# MICROCODE.net
KiCad netlist of a schematic drawn in EAGLE
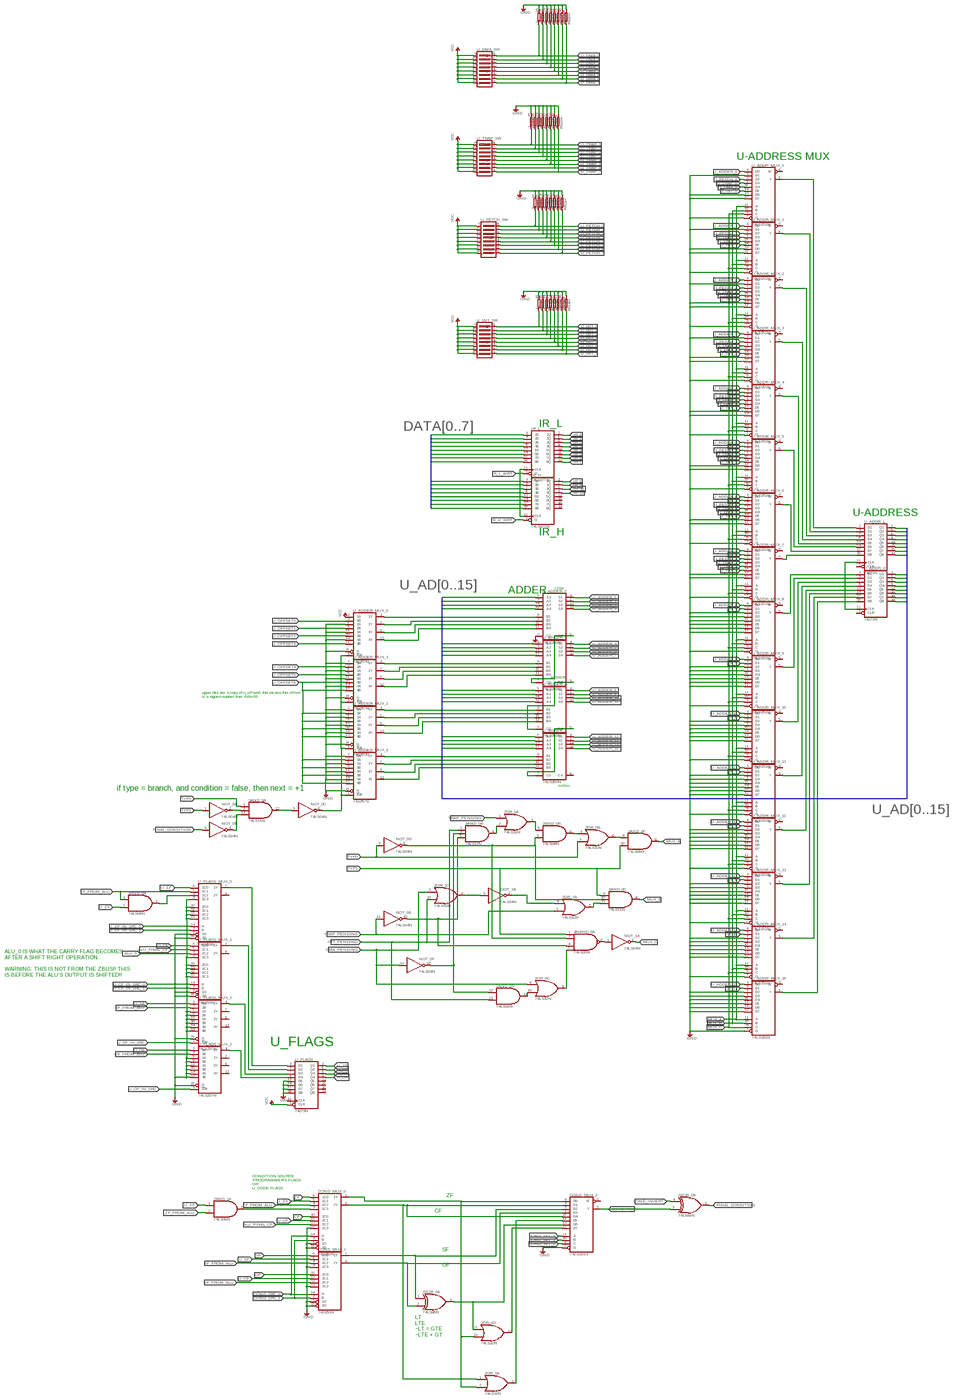
[diagram p0: schematic, sheet 1, overview]
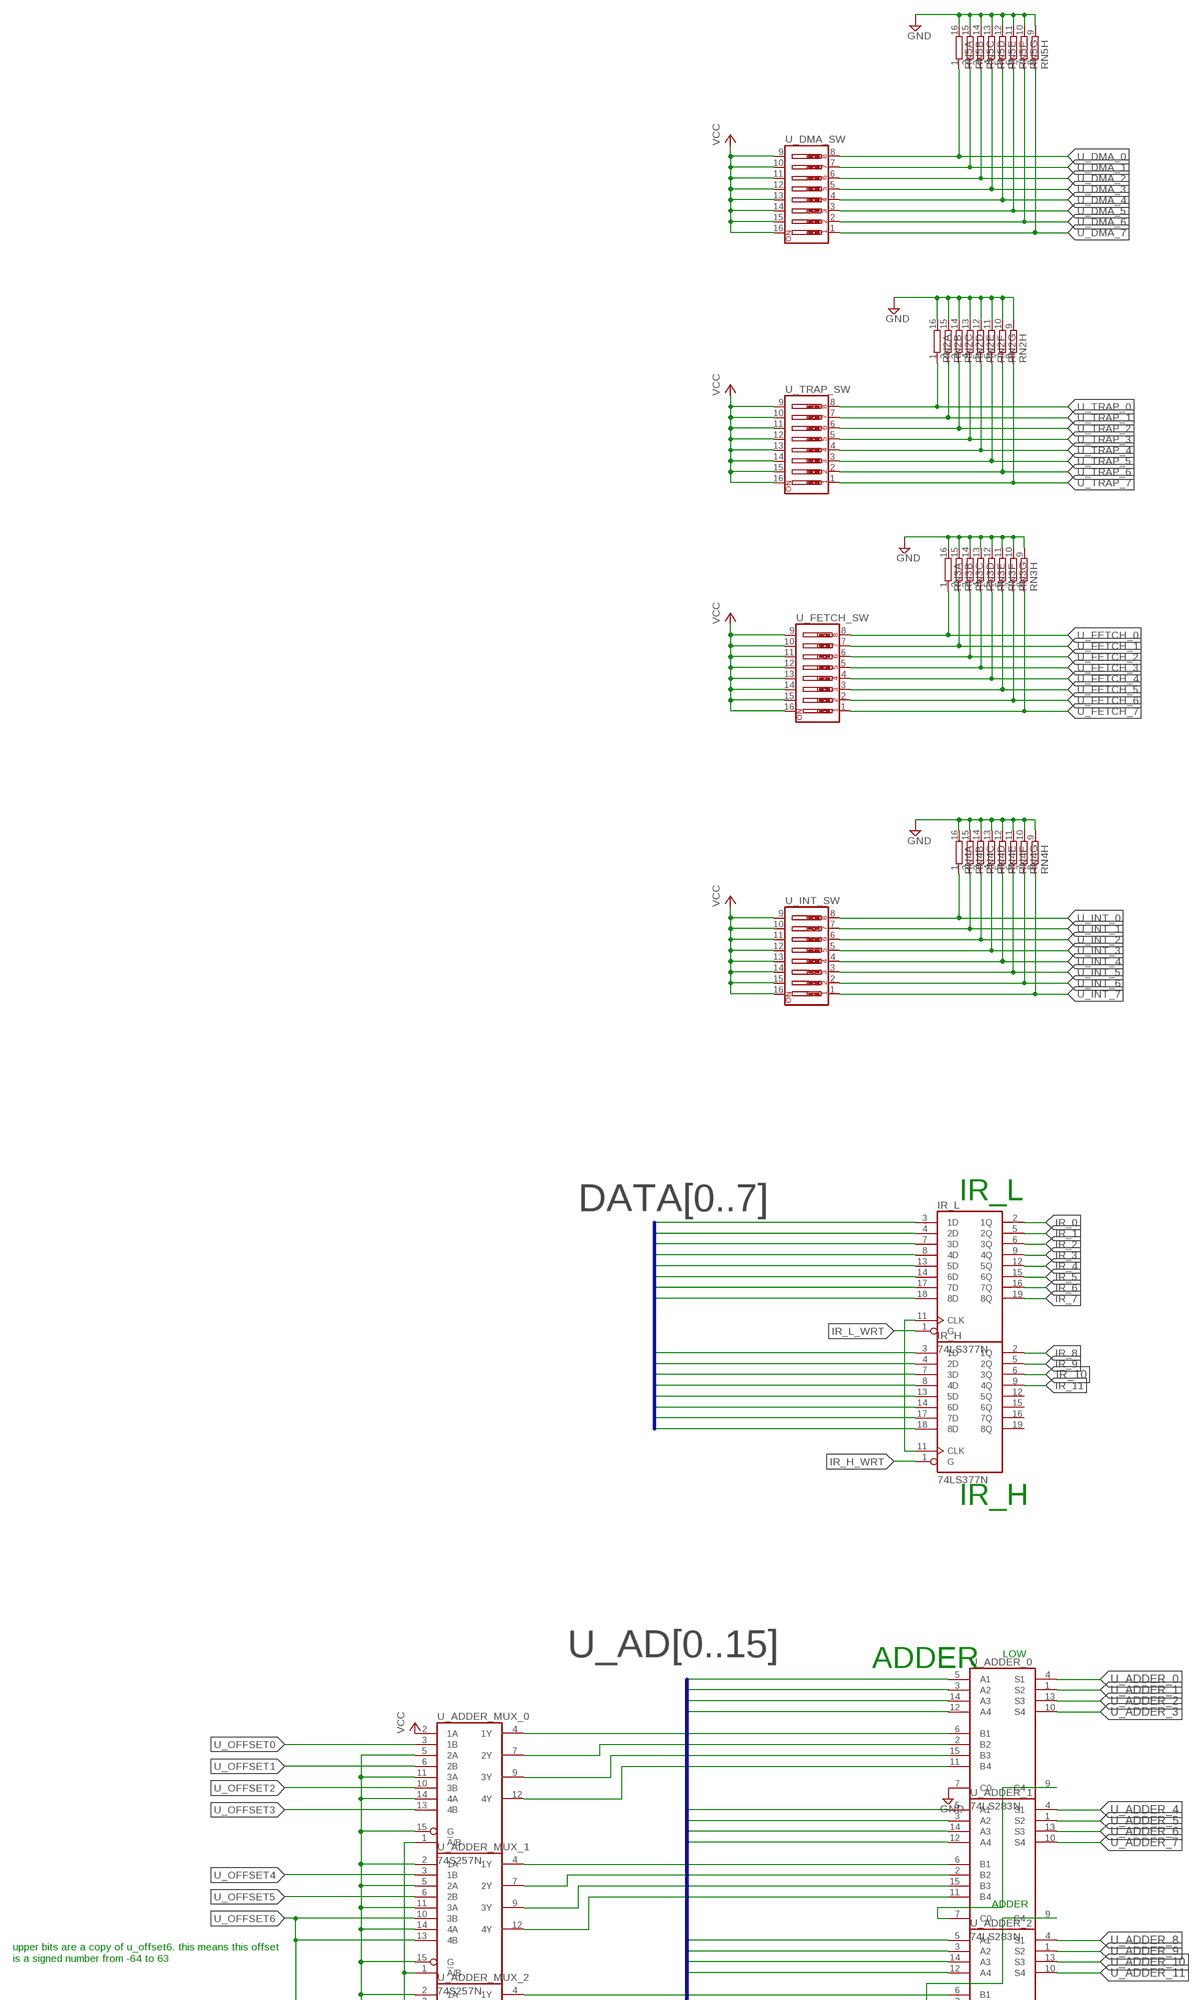
[diagram p1: schematic, sheet 1, part 1 of 4]
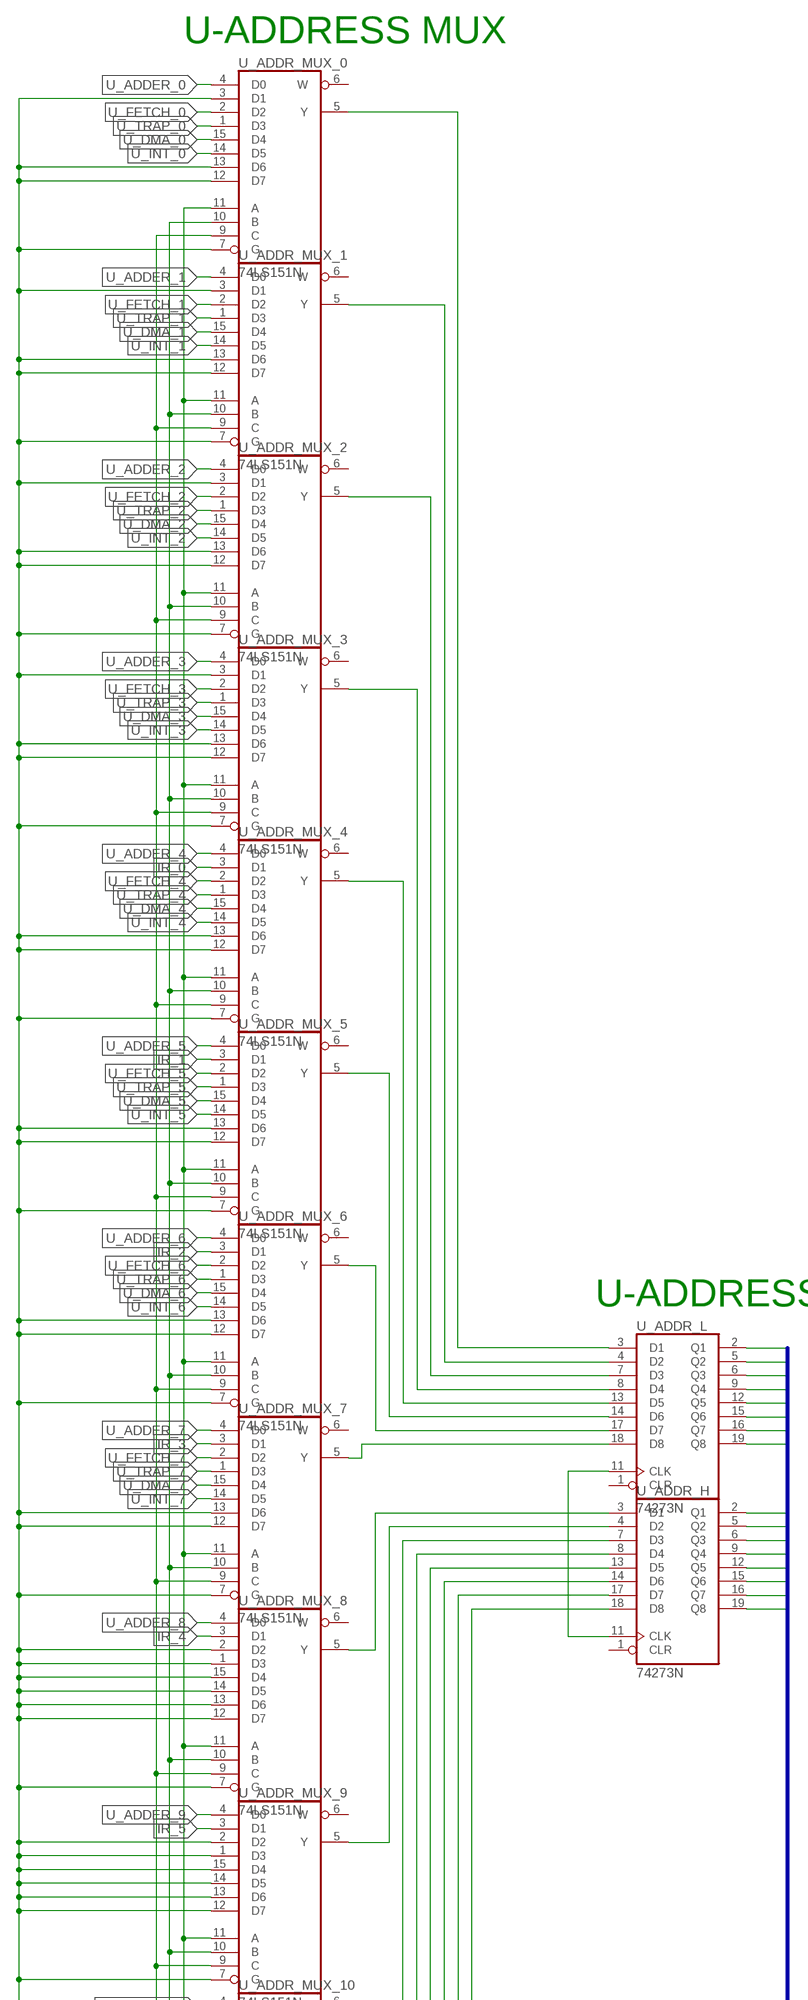
[diagram p2: schematic, sheet 1, part 2 of 4]
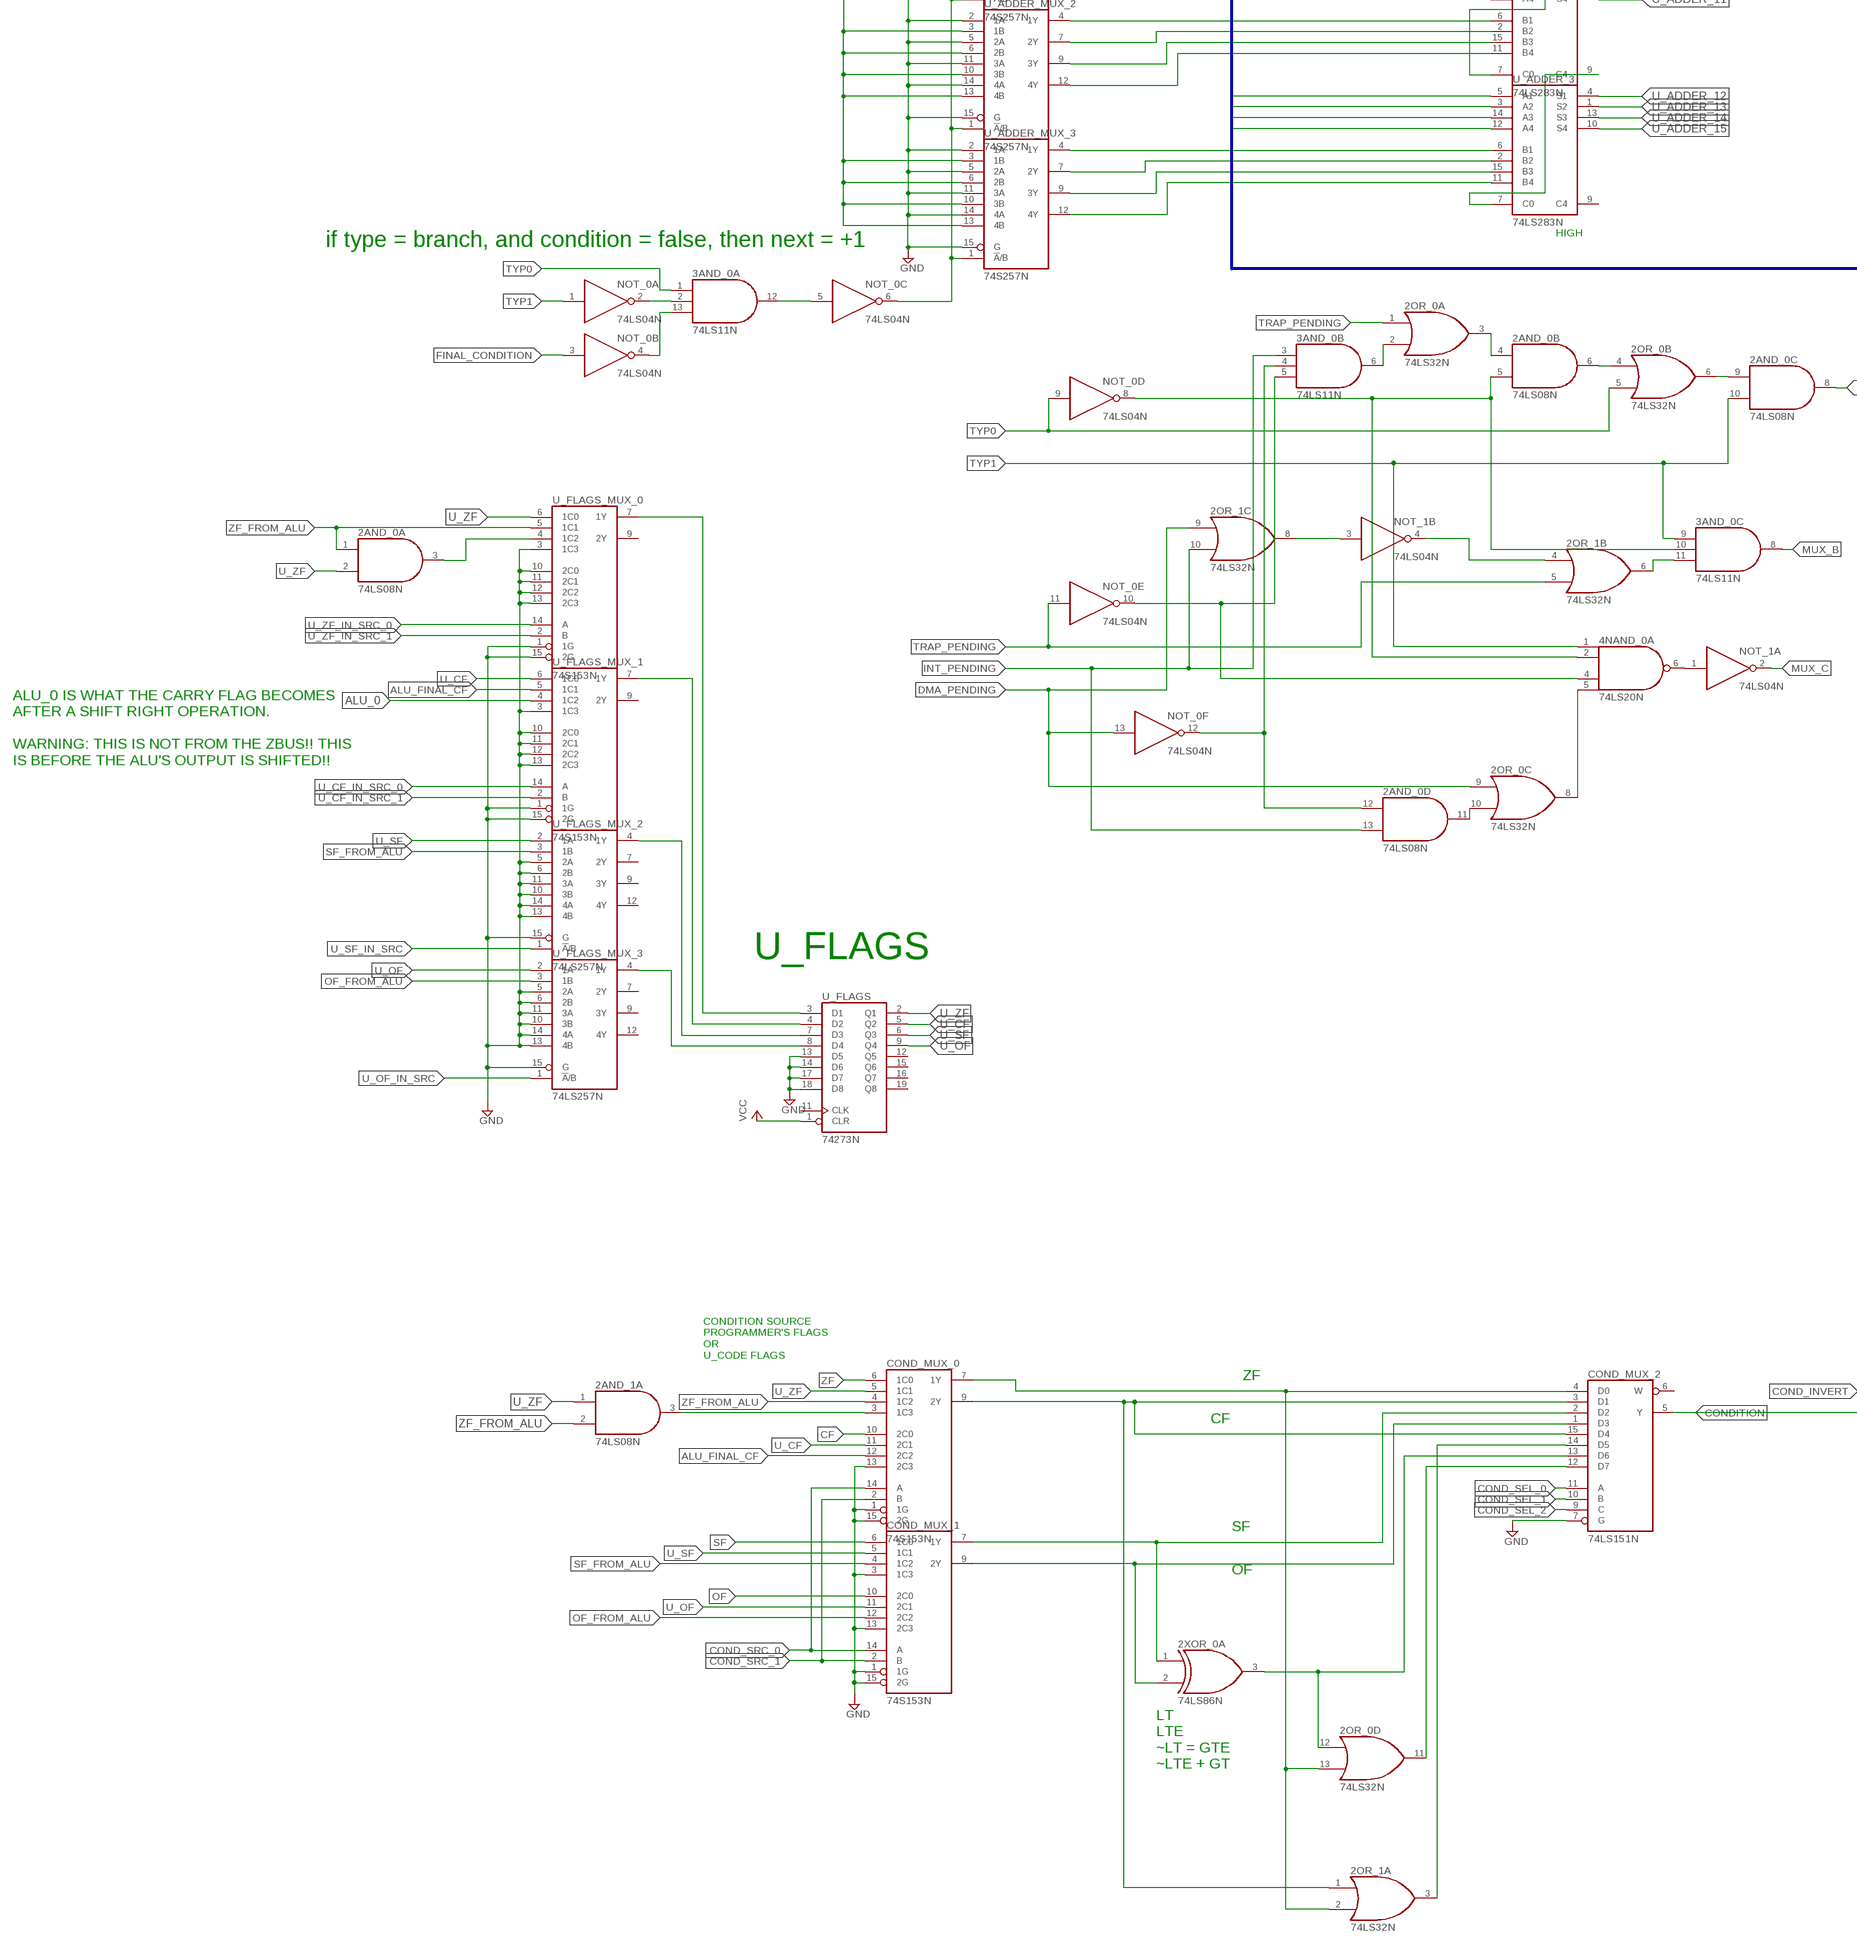
[diagram p3: schematic, sheet 1, part 3 of 4]
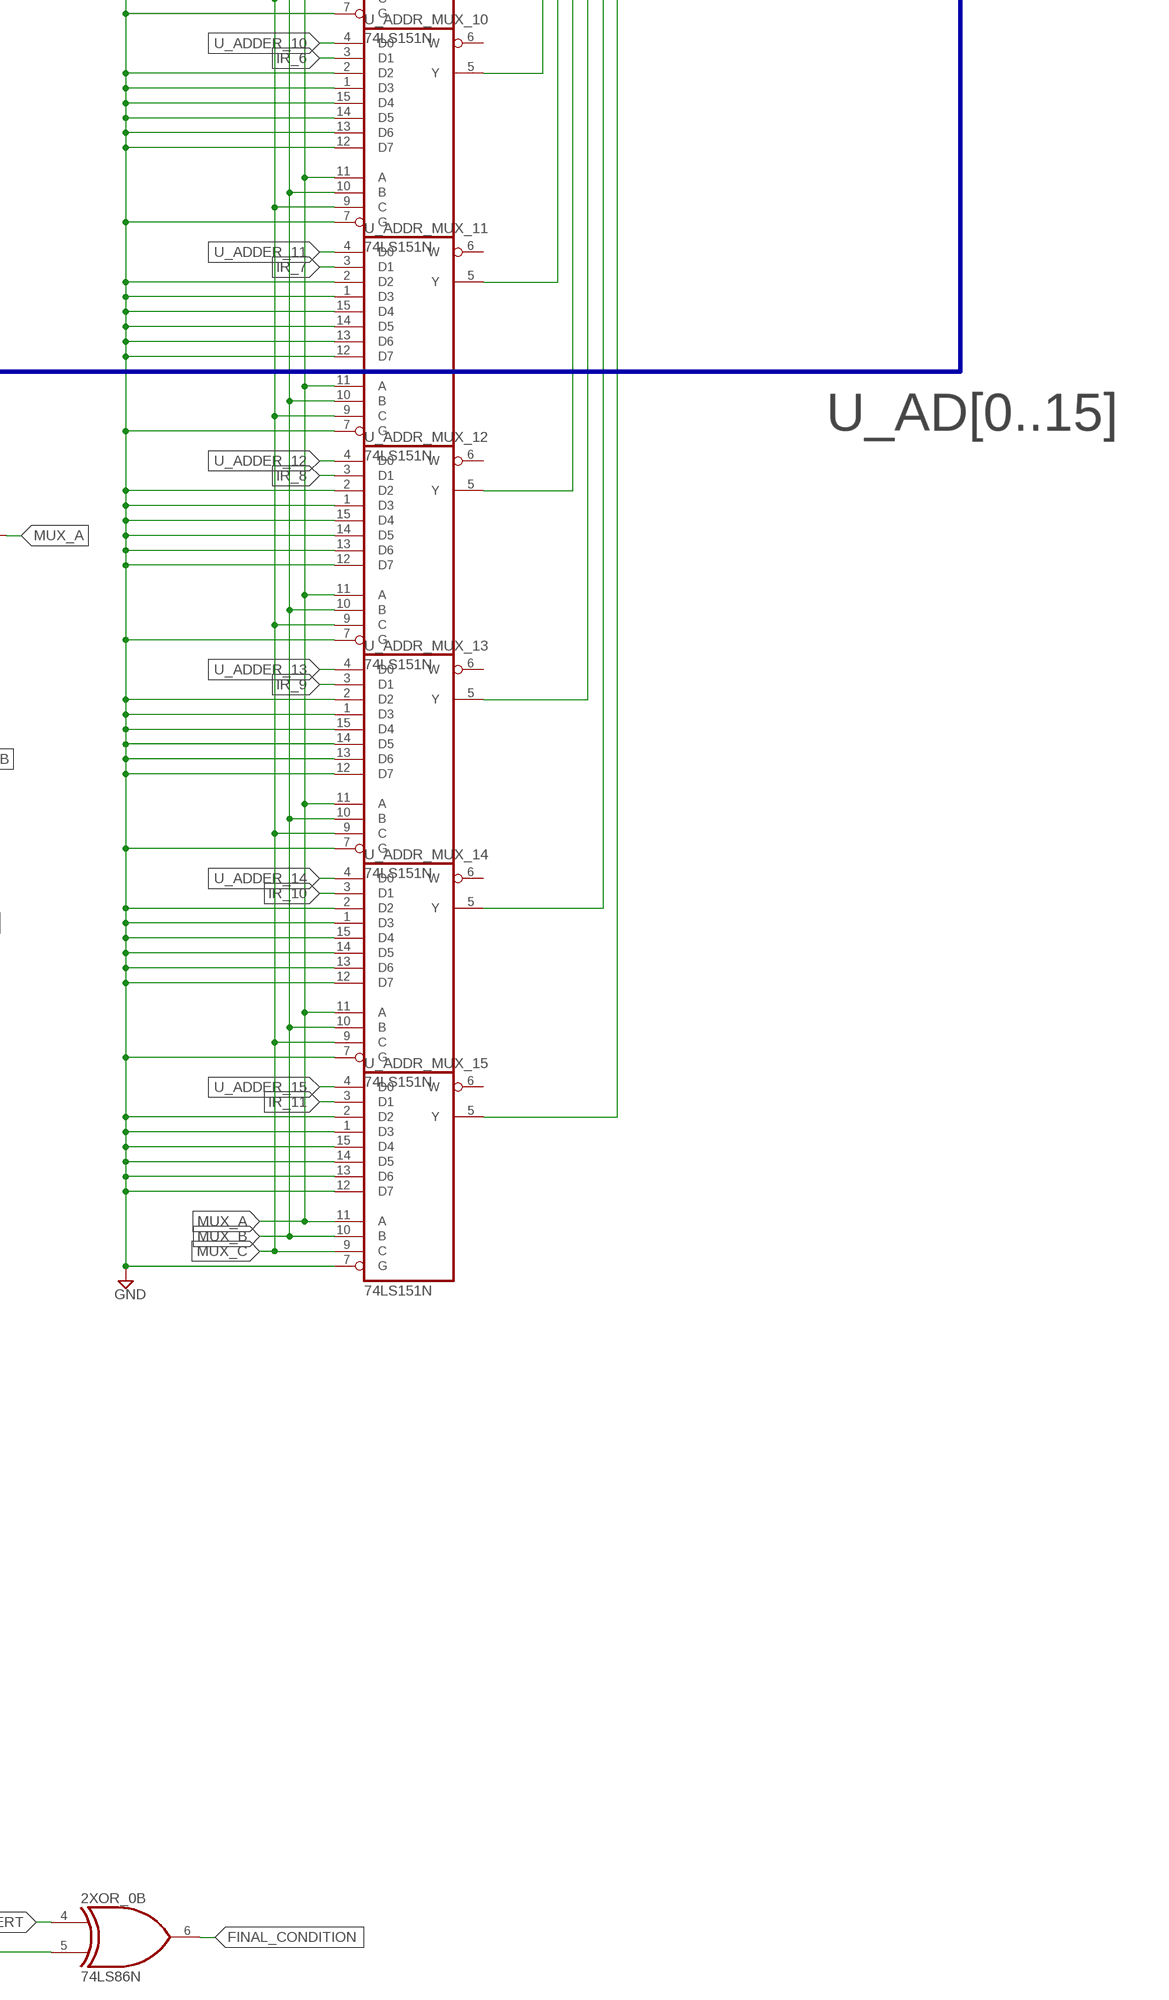
[diagram p4: schematic, sheet 1, part 4 of 4]

(export (version "E")
  (design (tool "Eeschema 10.0.6"))
  (components
    (comp (ref "2AND_0")
      (value "74LS08N")
      (footprint "eagle-import:DIL14")
      (libsource (lib "eagle-import") (part "7408NLS"))
    )
    (comp (ref "2AND_1")
      (value "74LS08N")
      (footprint "eagle-import:DIL14")
      (libsource (lib "eagle-import") (part "7408NLS"))
    )
    (comp (ref "2OR_0")
      (value "74LS32N")
      (footprint "eagle-import:DIL14")
      (libsource (lib "eagle-import") (part "7432NLS"))
    )
    (comp (ref "2OR_1")
      (value "74LS32N")
      (footprint "eagle-import:DIL14")
      (libsource (lib "eagle-import") (part "7432NLS"))
    )
    (comp (ref "2XOR_0")
      (value "74LS86N")
      (footprint "eagle-import:DIL14")
      (libsource (lib "eagle-import") (part "7486NLS"))
    )
    (comp (ref "3AND_0")
      (value "74LS11N")
      (footprint "eagle-import:DIL14")
      (libsource (lib "eagle-import") (part "7411NLS"))
    )
    (comp (ref "4NAND_0")
      (value "74LS20N")
      (footprint "eagle-import:DIL14")
      (libsource (lib "eagle-import") (part "7420NLS"))
    )
    (comp (ref "COND_MUX_0")
      (value "74S153N")
      (footprint "eagle-import:DIL16")
      (libsource (lib "eagle-import") (part "74153NS"))
    )
    (comp (ref "COND_MUX_1")
      (value "74S153N")
      (footprint "eagle-import:DIL16")
      (libsource (lib "eagle-import") (part "74153NS"))
    )
    (comp (ref "COND_MUX_2")
      (value "74LS151N")
      (footprint "eagle-import:DIL16")
      (libsource (lib "eagle-import") (part "74151NLS"))
    )
    (comp (ref "IR_H")
      (value "74LS377N")
      (footprint "eagle-import:DIL20")
      (libsource (lib "eagle-import") (part "74377NLS"))
    )
    (comp (ref "IR_L")
      (value "74LS377N")
      (footprint "eagle-import:DIL20")
      (libsource (lib "eagle-import") (part "74377NLS"))
    )
    (comp (ref "NOT_0")
      (value "74LS04N")
      (footprint "eagle-import:DIL14")
      (libsource (lib "eagle-import") (part "7404NLS"))
    )
    (comp (ref "NOT_1")
      (value "74LS04N")
      (footprint "eagle-import:DIL14")
      (libsource (lib "eagle-import") (part "7404NLS"))
    )
    (comp (ref "RN2")
      (value "8R-N")
      (footprint "eagle-import:DIL16")
      (libsource (lib "eagle-import") (part "8R-N"))
    )
    (comp (ref "RN3")
      (value "8R-N")
      (footprint "eagle-import:DIL16")
      (libsource (lib "eagle-import") (part "8R-N"))
    )
    (comp (ref "RN4")
      (value "8R-N")
      (footprint "eagle-import:DIL16")
      (libsource (lib "eagle-import") (part "8R-N"))
    )
    (comp (ref "RN5")
      (value "8R-N")
      (footprint "eagle-import:DIL16")
      (libsource (lib "eagle-import") (part "8R-N"))
    )
    (comp (ref "U_ADDER_0")
      (value "74LS283N")
      (footprint "eagle-import:DIL16")
      (libsource (lib "eagle-import") (part "74283NLS"))
    )
    (comp (ref "U_ADDER_1")
      (value "74LS283N")
      (footprint "eagle-import:DIL16")
      (libsource (lib "eagle-import") (part "74283NLS"))
    )
    (comp (ref "U_ADDER_2")
      (value "74LS283N")
      (footprint "eagle-import:DIL16")
      (libsource (lib "eagle-import") (part "74283NLS"))
    )
    (comp (ref "U_ADDER_3")
      (value "74LS283N")
      (footprint "eagle-import:DIL16")
      (libsource (lib "eagle-import") (part "74283NLS"))
    )
    (comp (ref "U_ADDER_MUX_0")
      (value "74S257N")
      (footprint "eagle-import:DIL16")
      (libsource (lib "eagle-import") (part "74257NS"))
    )
    (comp (ref "U_ADDER_MUX_1")
      (value "74S257N")
      (footprint "eagle-import:DIL16")
      (libsource (lib "eagle-import") (part "74257NS"))
    )
    (comp (ref "U_ADDER_MUX_2")
      (value "74S257N")
      (footprint "eagle-import:DIL16")
      (libsource (lib "eagle-import") (part "74257NS"))
    )
    (comp (ref "U_ADDER_MUX_3")
      (value "74S257N")
      (footprint "eagle-import:DIL16")
      (libsource (lib "eagle-import") (part "74257NS"))
    )
    (comp (ref "U_ADDR_H")
      (value "74273N")
      (footprint "eagle-import:DIL20")
      (libsource (lib "eagle-import") (part "74273N"))
    )
    (comp (ref "U_ADDR_L")
      (value "74273N")
      (footprint "eagle-import:DIL20")
      (libsource (lib "eagle-import") (part "74273N"))
    )
    (comp (ref "U_ADDR_MUX_0")
      (value "74LS151N")
      (footprint "eagle-import:DIL16")
      (libsource (lib "eagle-import") (part "74151NLS"))
    )
    (comp (ref "U_ADDR_MUX_1")
      (value "74LS151N")
      (footprint "eagle-import:DIL16")
      (libsource (lib "eagle-import") (part "74151NLS"))
    )
    (comp (ref "U_ADDR_MUX_2")
      (value "74LS151N")
      (footprint "eagle-import:DIL16")
      (libsource (lib "eagle-import") (part "74151NLS"))
    )
    (comp (ref "U_ADDR_MUX_3")
      (value "74LS151N")
      (footprint "eagle-import:DIL16")
      (libsource (lib "eagle-import") (part "74151NLS"))
    )
    (comp (ref "U_ADDR_MUX_4")
      (value "74LS151N")
      (footprint "eagle-import:DIL16")
      (libsource (lib "eagle-import") (part "74151NLS"))
    )
    (comp (ref "U_ADDR_MUX_5")
      (value "74LS151N")
      (footprint "eagle-import:DIL16")
      (libsource (lib "eagle-import") (part "74151NLS"))
    )
    (comp (ref "U_ADDR_MUX_6")
      (value "74LS151N")
      (footprint "eagle-import:DIL16")
      (libsource (lib "eagle-import") (part "74151NLS"))
    )
    (comp (ref "U_ADDR_MUX_7")
      (value "74LS151N")
      (footprint "eagle-import:DIL16")
      (libsource (lib "eagle-import") (part "74151NLS"))
    )
    (comp (ref "U_ADDR_MUX_8")
      (value "74LS151N")
      (footprint "eagle-import:DIL16")
      (libsource (lib "eagle-import") (part "74151NLS"))
    )
    (comp (ref "U_ADDR_MUX_9")
      (value "74LS151N")
      (footprint "eagle-import:DIL16")
      (libsource (lib "eagle-import") (part "74151NLS"))
    )
    (comp (ref "U_ADDR_MUX_10")
      (value "74LS151N")
      (footprint "eagle-import:DIL16")
      (libsource (lib "eagle-import") (part "74151NLS"))
    )
    (comp (ref "U_ADDR_MUX_11")
      (value "74LS151N")
      (footprint "eagle-import:DIL16")
      (libsource (lib "eagle-import") (part "74151NLS"))
    )
    (comp (ref "U_ADDR_MUX_12")
      (value "74LS151N")
      (footprint "eagle-import:DIL16")
      (libsource (lib "eagle-import") (part "74151NLS"))
    )
    (comp (ref "U_ADDR_MUX_13")
      (value "74LS151N")
      (footprint "eagle-import:DIL16")
      (libsource (lib "eagle-import") (part "74151NLS"))
    )
    (comp (ref "U_ADDR_MUX_14")
      (value "74LS151N")
      (footprint "eagle-import:DIL16")
      (libsource (lib "eagle-import") (part "74151NLS"))
    )
    (comp (ref "U_ADDR_MUX_15")
      (value "74LS151N")
      (footprint "eagle-import:DIL16")
      (libsource (lib "eagle-import") (part "74151NLS"))
    )
    (comp (ref "U_DMA_SW")
      (value "SW_DIP-8")
      (footprint "eagle-import:EDG-08")
      (libsource (lib "eagle-import") (part "SW_DIP-8"))
    )
    (comp (ref "U_FETCH_SW")
      (value "SW_DIP-8")
      (footprint "eagle-import:EDG-08")
      (libsource (lib "eagle-import") (part "SW_DIP-8"))
    )
    (comp (ref "U_FLAGS")
      (value "74273N")
      (footprint "eagle-import:DIL20")
      (libsource (lib "eagle-import") (part "74273N"))
    )
    (comp (ref "U_FLAGS_MUX_0")
      (value "74S153N")
      (footprint "eagle-import:DIL16")
      (libsource (lib "eagle-import") (part "74153NS"))
    )
    (comp (ref "U_FLAGS_MUX_1")
      (value "74S153N")
      (footprint "eagle-import:DIL16")
      (libsource (lib "eagle-import") (part "74153NS"))
    )
    (comp (ref "U_FLAGS_MUX_2")
      (value "74LS257N")
      (footprint "eagle-import:DIL16")
      (libsource (lib "eagle-import") (part "74257NLS"))
    )
    (comp (ref "U_FLAGS_MUX_3")
      (value "74LS257N")
      (footprint "eagle-import:DIL16")
      (libsource (lib "eagle-import") (part "74257NLS"))
    )
    (comp (ref "U_INT_SW")
      (value "SW_DIP-8")
      (footprint "eagle-import:EDG-08")
      (libsource (lib "eagle-import") (part "SW_DIP-8"))
    )
    (comp (ref "U_TRAP_SW")
      (value "SW_DIP-8")
      (footprint "eagle-import:EDG-08")
      (libsource (lib "eagle-import") (part "SW_DIP-8"))
    )
  )
  (nets
    (net (code "1") (name "/DATA0") (class "Default")
      (node (ref "IR_H") (pin "3") (pinfunction "1D_3") (pintype "input"))
      (node (ref "IR_L") (pin "3") (pinfunction "1D_3") (pintype "input"))
    )
    (net (code "2") (name "/DATA1") (class "Default")
      (node (ref "IR_H") (pin "4") (pinfunction "2D_4") (pintype "input"))
      (node (ref "IR_L") (pin "4") (pinfunction "2D_4") (pintype "input"))
    )
    (net (code "3") (name "/DATA2") (class "Default")
      (node (ref "IR_H") (pin "7") (pinfunction "3D_7") (pintype "input"))
      (node (ref "IR_L") (pin "7") (pinfunction "3D_7") (pintype "input"))
    )
    (net (code "4") (name "/DATA3") (class "Default")
      (node (ref "IR_H") (pin "8") (pinfunction "4D_8") (pintype "input"))
      (node (ref "IR_L") (pin "8") (pinfunction "4D_8") (pintype "input"))
    )
    (net (code "5") (name "/DATA4") (class "Default")
      (node (ref "IR_H") (pin "13") (pinfunction "5D_13") (pintype "input"))
      (node (ref "IR_L") (pin "13") (pinfunction "5D_13") (pintype "input"))
    )
    (net (code "6") (name "/DATA5") (class "Default")
      (node (ref "IR_H") (pin "14") (pinfunction "6D_14") (pintype "input"))
      (node (ref "IR_L") (pin "14") (pinfunction "6D_14") (pintype "input"))
    )
    (net (code "7") (name "/DATA6") (class "Default")
      (node (ref "IR_H") (pin "17") (pinfunction "7D_17") (pintype "input"))
      (node (ref "IR_L") (pin "17") (pinfunction "7D_17") (pintype "input"))
    )
    (net (code "8") (name "/DATA7") (class "Default")
      (node (ref "IR_H") (pin "18") (pinfunction "8D_18") (pintype "input"))
      (node (ref "IR_L") (pin "18") (pinfunction "8D_18") (pintype "input"))
    )
    (net (code "10") (name "/U_AD0") (class "Default")
      (node (ref "U_ADDER_0") (pin "5") (pinfunction "A1_5") (pintype "input"))
      (node (ref "U_ADDR_L") (pin "2") (pinfunction "Q1_2") (pintype "output"))
    )
    (net (code "11") (name "/U_AD1") (class "Default")
      (node (ref "U_ADDER_0") (pin "3") (pinfunction "A2_3") (pintype "input"))
      (node (ref "U_ADDR_L") (pin "5") (pinfunction "Q2_5") (pintype "output"))
    )
    (net (code "12") (name "/U_AD2") (class "Default")
      (node (ref "U_ADDER_0") (pin "14") (pinfunction "A3_14") (pintype "input"))
      (node (ref "U_ADDR_L") (pin "6") (pinfunction "Q3_6") (pintype "output"))
    )
    (net (code "13") (name "/U_AD3") (class "Default")
      (node (ref "U_ADDER_0") (pin "12") (pinfunction "A4_12") (pintype "input"))
      (node (ref "U_ADDR_L") (pin "9") (pinfunction "Q4_9") (pintype "output"))
    )
    (net (code "14") (name "/U_AD4") (class "Default")
      (node (ref "U_ADDER_1") (pin "5") (pinfunction "A1_5") (pintype "input"))
      (node (ref "U_ADDR_L") (pin "12") (pinfunction "Q5_12") (pintype "output"))
    )
    (net (code "15") (name "/U_AD5") (class "Default")
      (node (ref "U_ADDER_1") (pin "3") (pinfunction "A2_3") (pintype "input"))
      (node (ref "U_ADDR_L") (pin "15") (pinfunction "Q6_15") (pintype "output"))
    )
    (net (code "16") (name "/U_AD6") (class "Default")
      (node (ref "U_ADDER_1") (pin "14") (pinfunction "A3_14") (pintype "input"))
      (node (ref "U_ADDR_L") (pin "16") (pinfunction "Q7_16") (pintype "output"))
    )
    (net (code "17") (name "/U_AD7") (class "Default")
      (node (ref "U_ADDER_1") (pin "12") (pinfunction "A4_12") (pintype "input"))
      (node (ref "U_ADDR_L") (pin "19") (pinfunction "Q8_19") (pintype "output"))
    )
    (net (code "18") (name "/U_AD8") (class "Default")
      (node (ref "U_ADDER_2") (pin "5") (pinfunction "A1_5") (pintype "input"))
      (node (ref "U_ADDR_H") (pin "2") (pinfunction "Q1_2") (pintype "output"))
    )
    (net (code "19") (name "/U_AD9") (class "Default")
      (node (ref "U_ADDER_2") (pin "3") (pinfunction "A2_3") (pintype "input"))
      (node (ref "U_ADDR_H") (pin "5") (pinfunction "Q2_5") (pintype "output"))
    )
    (net (code "20") (name "/U_AD10") (class "Default")
      (node (ref "U_ADDER_2") (pin "14") (pinfunction "A3_14") (pintype "input"))
      (node (ref "U_ADDR_H") (pin "6") (pinfunction "Q3_6") (pintype "output"))
    )
    (net (code "21") (name "/U_AD11") (class "Default")
      (node (ref "U_ADDER_2") (pin "12") (pinfunction "A4_12") (pintype "input"))
      (node (ref "U_ADDR_H") (pin "9") (pinfunction "Q4_9") (pintype "output"))
    )
    (net (code "22") (name "/U_AD12") (class "Default")
      (node (ref "U_ADDER_3") (pin "5") (pinfunction "A1_5") (pintype "input"))
      (node (ref "U_ADDR_H") (pin "12") (pinfunction "Q5_12") (pintype "output"))
    )
    (net (code "23") (name "/U_AD13") (class "Default")
      (node (ref "U_ADDER_3") (pin "3") (pinfunction "A2_3") (pintype "input"))
      (node (ref "U_ADDR_H") (pin "15") (pinfunction "Q6_15") (pintype "output"))
    )
    (net (code "24") (name "/U_AD14") (class "Default")
      (node (ref "U_ADDER_3") (pin "14") (pinfunction "A3_14") (pintype "input"))
      (node (ref "U_ADDR_H") (pin "16") (pinfunction "Q7_16") (pintype "output"))
    )
    (net (code "25") (name "/U_AD15") (class "Default")
      (node (ref "U_ADDER_3") (pin "12") (pinfunction "A4_12") (pintype "input"))
      (node (ref "U_ADDR_H") (pin "19") (pinfunction "Q8_19") (pintype "output"))
    )
    (net (code "27") (name "ALU_0") (class "Default")
      (node (ref "U_FLAGS_MUX_1") (pin "4") (pinfunction "1C2_4") (pintype "input"))
    )
    (net (code "28") (name "ALU_FINAL_CF") (class "Default")
      (node (ref "COND_MUX_0") (pin "12") (pinfunction "2C2_12") (pintype "input"))
      (node (ref "U_FLAGS_MUX_1") (pin "5") (pinfunction "1C1_5") (pintype "input"))
    )
    (net (code "29") (name "CF") (class "Default")
      (node (ref "COND_MUX_0") (pin "10") (pinfunction "2C0_10") (pintype "input"))
    )
    (net (code "30") (name "CONDITION") (class "Default")
      (node (ref "2XOR_0") (pin "5") (pinfunction "I1_5") (pintype "input"))
      (node (ref "COND_MUX_2") (pin "5") (pinfunction "Y_5") (pintype "output"))
    )
    (net (code "31") (name "COND_INVERT") (class "Default")
      (node (ref "2XOR_0") (pin "4") (pinfunction "I0_4") (pintype "input"))
    )
    (net (code "32") (name "COND_SEL_0") (class "Default")
      (node (ref "COND_MUX_2") (pin "11") (pinfunction "A_11") (pintype "input"))
    )
    (net (code "33") (name "COND_SEL_1") (class "Default")
      (node (ref "COND_MUX_2") (pin "10") (pinfunction "B_10") (pintype "input"))
    )
    (net (code "34") (name "COND_SEL_2") (class "Default")
      (node (ref "COND_MUX_2") (pin "9") (pinfunction "C_9") (pintype "input"))
    )
    (net (code "35") (name "COND_SRC_0") (class "Default")
      (node (ref "COND_MUX_0") (pin "14") (pinfunction "A_14") (pintype "input"))
      (node (ref "COND_MUX_1") (pin "14") (pinfunction "A_14") (pintype "input"))
    )
    (net (code "36") (name "COND_SRC_1") (class "Default")
      (node (ref "COND_MUX_0") (pin "2") (pinfunction "B_2") (pintype "input"))
      (node (ref "COND_MUX_1") (pin "2") (pinfunction "B_2") (pintype "input"))
    )
    (net (code "37") (name "DMA_PENDING") (class "Default")
      (node (ref "2OR_0") (pin "9") (pinfunction "I0_9") (pintype "input"))
      (node (ref "2OR_1") (pin "9") (pinfunction "I0_9") (pintype "input"))
      (node (ref "NOT_0") (pin "13") (pinfunction "I_13") (pintype "input"))
    )
    (net (code "38") (name "FINAL_CONDITION") (class "Default")
      (node (ref "2XOR_0") (pin "6") (pinfunction "O_6") (pintype "output"))
      (node (ref "NOT_0") (pin "3") (pinfunction "I_3") (pintype "input"))
    )
    (net (code "39") (name "GND") (class "Default")
      (node (ref "COND_MUX_0") (pin "1") (pinfunction "1G_1") (pintype "input"))
      (node (ref "COND_MUX_0") (pin "13") (pinfunction "2C3_13") (pintype "input"))
      (node (ref "COND_MUX_0") (pin "15") (pinfunction "2G_15") (pintype "input"))
      (node (ref "COND_MUX_1") (pin "1") (pinfunction "1G_1") (pintype "input"))
      (node (ref "COND_MUX_1") (pin "13") (pinfunction "2C3_13") (pintype "input"))
      (node (ref "COND_MUX_1") (pin "15") (pinfunction "2G_15") (pintype "input"))
      (node (ref "COND_MUX_1") (pin "3") (pinfunction "1C3_3") (pintype "input"))
      (node (ref "COND_MUX_2") (pin "7") (pinfunction "G_7") (pintype "input"))
      (node (ref "RN2") (pin "10") (pinfunction "2_10") (pintype "passive"))
      (node (ref "RN2") (pin "11") (pinfunction "2_11") (pintype "passive"))
      (node (ref "RN2") (pin "12") (pinfunction "2_12") (pintype "passive"))
      (node (ref "RN2") (pin "13") (pinfunction "2_13") (pintype "passive"))
      (node (ref "RN2") (pin "14") (pinfunction "2_14") (pintype "passive"))
      (node (ref "RN2") (pin "15") (pinfunction "2_15") (pintype "passive"))
      (node (ref "RN2") (pin "16") (pinfunction "2_16") (pintype "passive"))
      (node (ref "RN2") (pin "9") (pinfunction "2_9") (pintype "passive"))
      (node (ref "RN3") (pin "10") (pinfunction "2_10") (pintype "passive"))
      (node (ref "RN3") (pin "11") (pinfunction "2_11") (pintype "passive"))
      (node (ref "RN3") (pin "12") (pinfunction "2_12") (pintype "passive"))
      (node (ref "RN3") (pin "13") (pinfunction "2_13") (pintype "passive"))
      (node (ref "RN3") (pin "14") (pinfunction "2_14") (pintype "passive"))
      (node (ref "RN3") (pin "15") (pinfunction "2_15") (pintype "passive"))
      (node (ref "RN3") (pin "16") (pinfunction "2_16") (pintype "passive"))
      (node (ref "RN3") (pin "9") (pinfunction "2_9") (pintype "passive"))
      (node (ref "RN4") (pin "10") (pinfunction "2_10") (pintype "passive"))
      (node (ref "RN4") (pin "11") (pinfunction "2_11") (pintype "passive"))
      (node (ref "RN4") (pin "12") (pinfunction "2_12") (pintype "passive"))
      (node (ref "RN4") (pin "13") (pinfunction "2_13") (pintype "passive"))
      (node (ref "RN4") (pin "14") (pinfunction "2_14") (pintype "passive"))
      (node (ref "RN4") (pin "15") (pinfunction "2_15") (pintype "passive"))
      (node (ref "RN4") (pin "16") (pinfunction "2_16") (pintype "passive"))
      (node (ref "RN4") (pin "9") (pinfunction "2_9") (pintype "passive"))
      (node (ref "RN5") (pin "10") (pinfunction "2_10") (pintype "passive"))
      (node (ref "RN5") (pin "11") (pinfunction "2_11") (pintype "passive"))
      (node (ref "RN5") (pin "12") (pinfunction "2_12") (pintype "passive"))
      (node (ref "RN5") (pin "13") (pinfunction "2_13") (pintype "passive"))
      (node (ref "RN5") (pin "14") (pinfunction "2_14") (pintype "passive"))
      (node (ref "RN5") (pin "15") (pinfunction "2_15") (pintype "passive"))
      (node (ref "RN5") (pin "16") (pinfunction "2_16") (pintype "passive"))
      (node (ref "RN5") (pin "9") (pinfunction "2_9") (pintype "passive"))
      (node (ref "U_ADDER_0") (pin "7") (pinfunction "C0_7") (pintype "input"))
      (node (ref "U_ADDER_MUX_0") (pin "11") (pinfunction "3A_11") (pintype "input"))
      (node (ref "U_ADDER_MUX_0") (pin "14") (pinfunction "4A_14") (pintype "input"))
      (node (ref "U_ADDER_MUX_0") (pin "15") (pinfunction "G_15") (pintype "input"))
      (node (ref "U_ADDER_MUX_0") (pin "5") (pinfunction "2A_5") (pintype "input"))
      (node (ref "U_ADDER_MUX_1") (pin "11") (pinfunction "3A_11") (pintype "input"))
      (node (ref "U_ADDER_MUX_1") (pin "14") (pinfunction "4A_14") (pintype "input"))
      (node (ref "U_ADDER_MUX_1") (pin "15") (pinfunction "G_15") (pintype "input"))
      (node (ref "U_ADDER_MUX_1") (pin "2") (pinfunction "1A_2") (pintype "input"))
      (node (ref "U_ADDER_MUX_1") (pin "5") (pinfunction "2A_5") (pintype "input"))
      (node (ref "U_ADDER_MUX_2") (pin "11") (pinfunction "3A_11") (pintype "input"))
      (node (ref "U_ADDER_MUX_2") (pin "14") (pinfunction "4A_14") (pintype "input"))
      (node (ref "U_ADDER_MUX_2") (pin "15") (pinfunction "G_15") (pintype "input"))
      (node (ref "U_ADDER_MUX_2") (pin "2") (pinfunction "1A_2") (pintype "input"))
      (node (ref "U_ADDER_MUX_2") (pin "5") (pinfunction "2A_5") (pintype "input"))
      (node (ref "U_ADDER_MUX_3") (pin "11") (pinfunction "3A_11") (pintype "input"))
      (node (ref "U_ADDER_MUX_3") (pin "14") (pinfunction "4A_14") (pintype "input"))
      (node (ref "U_ADDER_MUX_3") (pin "15") (pinfunction "G_15") (pintype "input"))
      (node (ref "U_ADDER_MUX_3") (pin "2") (pinfunction "1A_2") (pintype "input"))
      (node (ref "U_ADDER_MUX_3") (pin "5") (pinfunction "2A_5") (pintype "input"))
      (node (ref "U_ADDR_MUX_0") (pin "12") (pinfunction "D7_12") (pintype "input"))
      (node (ref "U_ADDR_MUX_0") (pin "13") (pinfunction "D6_13") (pintype "input"))
      (node (ref "U_ADDR_MUX_0") (pin "3") (pinfunction "D1_3") (pintype "input"))
      (node (ref "U_ADDR_MUX_0") (pin "7") (pinfunction "G_7") (pintype "input"))
      (node (ref "U_ADDR_MUX_1") (pin "12") (pinfunction "D7_12") (pintype "input"))
      (node (ref "U_ADDR_MUX_1") (pin "13") (pinfunction "D6_13") (pintype "input"))
      (node (ref "U_ADDR_MUX_1") (pin "3") (pinfunction "D1_3") (pintype "input"))
      (node (ref "U_ADDR_MUX_1") (pin "7") (pinfunction "G_7") (pintype "input"))
      (node (ref "U_ADDR_MUX_10") (pin "1") (pinfunction "D3_1") (pintype "input"))
      (node (ref "U_ADDR_MUX_10") (pin "12") (pinfunction "D7_12") (pintype "input"))
      (node (ref "U_ADDR_MUX_10") (pin "13") (pinfunction "D6_13") (pintype "input"))
      (node (ref "U_ADDR_MUX_10") (pin "14") (pinfunction "D5_14") (pintype "input"))
      (node (ref "U_ADDR_MUX_10") (pin "15") (pinfunction "D4_15") (pintype "input"))
      (node (ref "U_ADDR_MUX_10") (pin "2") (pinfunction "D2_2") (pintype "input"))
      (node (ref "U_ADDR_MUX_10") (pin "7") (pinfunction "G_7") (pintype "input"))
      (node (ref "U_ADDR_MUX_11") (pin "1") (pinfunction "D3_1") (pintype "input"))
      (node (ref "U_ADDR_MUX_11") (pin "12") (pinfunction "D7_12") (pintype "input"))
      (node (ref "U_ADDR_MUX_11") (pin "13") (pinfunction "D6_13") (pintype "input"))
      (node (ref "U_ADDR_MUX_11") (pin "14") (pinfunction "D5_14") (pintype "input"))
      (node (ref "U_ADDR_MUX_11") (pin "15") (pinfunction "D4_15") (pintype "input"))
      (node (ref "U_ADDR_MUX_11") (pin "2") (pinfunction "D2_2") (pintype "input"))
      (node (ref "U_ADDR_MUX_11") (pin "7") (pinfunction "G_7") (pintype "input"))
      (node (ref "U_ADDR_MUX_12") (pin "1") (pinfunction "D3_1") (pintype "input"))
      (node (ref "U_ADDR_MUX_12") (pin "12") (pinfunction "D7_12") (pintype "input"))
      (node (ref "U_ADDR_MUX_12") (pin "13") (pinfunction "D6_13") (pintype "input"))
      (node (ref "U_ADDR_MUX_12") (pin "14") (pinfunction "D5_14") (pintype "input"))
      (node (ref "U_ADDR_MUX_12") (pin "15") (pinfunction "D4_15") (pintype "input"))
      (node (ref "U_ADDR_MUX_12") (pin "2") (pinfunction "D2_2") (pintype "input"))
      (node (ref "U_ADDR_MUX_12") (pin "7") (pinfunction "G_7") (pintype "input"))
      (node (ref "U_ADDR_MUX_13") (pin "1") (pinfunction "D3_1") (pintype "input"))
      (node (ref "U_ADDR_MUX_13") (pin "12") (pinfunction "D7_12") (pintype "input"))
      (node (ref "U_ADDR_MUX_13") (pin "13") (pinfunction "D6_13") (pintype "input"))
      (node (ref "U_ADDR_MUX_13") (pin "14") (pinfunction "D5_14") (pintype "input"))
      (node (ref "U_ADDR_MUX_13") (pin "15") (pinfunction "D4_15") (pintype "input"))
      (node (ref "U_ADDR_MUX_13") (pin "2") (pinfunction "D2_2") (pintype "input"))
      (node (ref "U_ADDR_MUX_13") (pin "7") (pinfunction "G_7") (pintype "input"))
      (node (ref "U_ADDR_MUX_14") (pin "1") (pinfunction "D3_1") (pintype "input"))
      (node (ref "U_ADDR_MUX_14") (pin "12") (pinfunction "D7_12") (pintype "input"))
      (node (ref "U_ADDR_MUX_14") (pin "13") (pinfunction "D6_13") (pintype "input"))
      (node (ref "U_ADDR_MUX_14") (pin "14") (pinfunction "D5_14") (pintype "input"))
      (node (ref "U_ADDR_MUX_14") (pin "15") (pinfunction "D4_15") (pintype "input"))
      (node (ref "U_ADDR_MUX_14") (pin "2") (pinfunction "D2_2") (pintype "input"))
      (node (ref "U_ADDR_MUX_14") (pin "7") (pinfunction "G_7") (pintype "input"))
      (node (ref "U_ADDR_MUX_15") (pin "1") (pinfunction "D3_1") (pintype "input"))
      (node (ref "U_ADDR_MUX_15") (pin "12") (pinfunction "D7_12") (pintype "input"))
      (node (ref "U_ADDR_MUX_15") (pin "13") (pinfunction "D6_13") (pintype "input"))
      (node (ref "U_ADDR_MUX_15") (pin "14") (pinfunction "D5_14") (pintype "input"))
      (node (ref "U_ADDR_MUX_15") (pin "15") (pinfunction "D4_15") (pintype "input"))
      (node (ref "U_ADDR_MUX_15") (pin "2") (pinfunction "D2_2") (pintype "input"))
      (node (ref "U_ADDR_MUX_15") (pin "7") (pinfunction "G_7") (pintype "input"))
      (node (ref "U_ADDR_MUX_2") (pin "12") (pinfunction "D7_12") (pintype "input"))
      (node (ref "U_ADDR_MUX_2") (pin "13") (pinfunction "D6_13") (pintype "input"))
      (node (ref "U_ADDR_MUX_2") (pin "3") (pinfunction "D1_3") (pintype "input"))
      (node (ref "U_ADDR_MUX_2") (pin "7") (pinfunction "G_7") (pintype "input"))
      (node (ref "U_ADDR_MUX_3") (pin "12") (pinfunction "D7_12") (pintype "input"))
      (node (ref "U_ADDR_MUX_3") (pin "13") (pinfunction "D6_13") (pintype "input"))
      (node (ref "U_ADDR_MUX_3") (pin "3") (pinfunction "D1_3") (pintype "input"))
      (node (ref "U_ADDR_MUX_3") (pin "7") (pinfunction "G_7") (pintype "input"))
      (node (ref "U_ADDR_MUX_4") (pin "12") (pinfunction "D7_12") (pintype "input"))
      (node (ref "U_ADDR_MUX_4") (pin "13") (pinfunction "D6_13") (pintype "input"))
      (node (ref "U_ADDR_MUX_4") (pin "7") (pinfunction "G_7") (pintype "input"))
      (node (ref "U_ADDR_MUX_5") (pin "12") (pinfunction "D7_12") (pintype "input"))
      (node (ref "U_ADDR_MUX_5") (pin "13") (pinfunction "D6_13") (pintype "input"))
      (node (ref "U_ADDR_MUX_5") (pin "7") (pinfunction "G_7") (pintype "input"))
      (node (ref "U_ADDR_MUX_6") (pin "12") (pinfunction "D7_12") (pintype "input"))
      (node (ref "U_ADDR_MUX_6") (pin "13") (pinfunction "D6_13") (pintype "input"))
      (node (ref "U_ADDR_MUX_6") (pin "7") (pinfunction "G_7") (pintype "input"))
      (node (ref "U_ADDR_MUX_7") (pin "12") (pinfunction "D7_12") (pintype "input"))
      (node (ref "U_ADDR_MUX_7") (pin "13") (pinfunction "D6_13") (pintype "input"))
      (node (ref "U_ADDR_MUX_7") (pin "7") (pinfunction "G_7") (pintype "input"))
      (node (ref "U_ADDR_MUX_8") (pin "1") (pinfunction "D3_1") (pintype "input"))
      (node (ref "U_ADDR_MUX_8") (pin "12") (pinfunction "D7_12") (pintype "input"))
      (node (ref "U_ADDR_MUX_8") (pin "13") (pinfunction "D6_13") (pintype "input"))
      (node (ref "U_ADDR_MUX_8") (pin "14") (pinfunction "D5_14") (pintype "input"))
      (node (ref "U_ADDR_MUX_8") (pin "15") (pinfunction "D4_15") (pintype "input"))
      (node (ref "U_ADDR_MUX_8") (pin "2") (pinfunction "D2_2") (pintype "input"))
      (node (ref "U_ADDR_MUX_8") (pin "7") (pinfunction "G_7") (pintype "input"))
      (node (ref "U_ADDR_MUX_9") (pin "1") (pinfunction "D3_1") (pintype "input"))
      (node (ref "U_ADDR_MUX_9") (pin "12") (pinfunction "D7_12") (pintype "input"))
      (node (ref "U_ADDR_MUX_9") (pin "13") (pinfunction "D6_13") (pintype "input"))
      (node (ref "U_ADDR_MUX_9") (pin "14") (pinfunction "D5_14") (pintype "input"))
      (node (ref "U_ADDR_MUX_9") (pin "15") (pinfunction "D4_15") (pintype "input"))
      (node (ref "U_ADDR_MUX_9") (pin "2") (pinfunction "D2_2") (pintype "input"))
      (node (ref "U_ADDR_MUX_9") (pin "7") (pinfunction "G_7") (pintype "input"))
      (node (ref "U_FLAGS") (pin "13") (pinfunction "D5_13") (pintype "input"))
      (node (ref "U_FLAGS") (pin "14") (pinfunction "D6_14") (pintype "input"))
      (node (ref "U_FLAGS") (pin "17") (pinfunction "D7_17") (pintype "input"))
      (node (ref "U_FLAGS") (pin "18") (pinfunction "D8_18") (pintype "input"))
      (node (ref "U_FLAGS_MUX_0") (pin "1") (pinfunction "1G_1") (pintype "input"))
      (node (ref "U_FLAGS_MUX_0") (pin "10") (pinfunction "2C0_10") (pintype "input"))
      (node (ref "U_FLAGS_MUX_0") (pin "11") (pinfunction "2C1_11") (pintype "input"))
      (node (ref "U_FLAGS_MUX_0") (pin "12") (pinfunction "2C2_12") (pintype "input"))
      (node (ref "U_FLAGS_MUX_0") (pin "13") (pinfunction "2C3_13") (pintype "input"))
      (node (ref "U_FLAGS_MUX_0") (pin "15") (pinfunction "2G_15") (pintype "input"))
      (node (ref "U_FLAGS_MUX_0") (pin "3") (pinfunction "1C3_3") (pintype "input"))
      (node (ref "U_FLAGS_MUX_1") (pin "1") (pinfunction "1G_1") (pintype "input"))
      (node (ref "U_FLAGS_MUX_1") (pin "10") (pinfunction "2C0_10") (pintype "input"))
      (node (ref "U_FLAGS_MUX_1") (pin "11") (pinfunction "2C1_11") (pintype "input"))
      (node (ref "U_FLAGS_MUX_1") (pin "12") (pinfunction "2C2_12") (pintype "input"))
      (node (ref "U_FLAGS_MUX_1") (pin "13") (pinfunction "2C3_13") (pintype "input"))
      (node (ref "U_FLAGS_MUX_1") (pin "15") (pinfunction "2G_15") (pintype "input"))
      (node (ref "U_FLAGS_MUX_1") (pin "3") (pinfunction "1C3_3") (pintype "input"))
      (node (ref "U_FLAGS_MUX_2") (pin "10") (pinfunction "3B_10") (pintype "input"))
      (node (ref "U_FLAGS_MUX_2") (pin "11") (pinfunction "3A_11") (pintype "input"))
      (node (ref "U_FLAGS_MUX_2") (pin "13") (pinfunction "4B_13") (pintype "input"))
      (node (ref "U_FLAGS_MUX_2") (pin "14") (pinfunction "4A_14") (pintype "input"))
      (node (ref "U_FLAGS_MUX_2") (pin "15") (pinfunction "G_15") (pintype "input"))
      (node (ref "U_FLAGS_MUX_2") (pin "5") (pinfunction "2A_5") (pintype "input"))
      (node (ref "U_FLAGS_MUX_2") (pin "6") (pinfunction "2B_6") (pintype "input"))
      (node (ref "U_FLAGS_MUX_3") (pin "10") (pinfunction "3B_10") (pintype "input"))
      (node (ref "U_FLAGS_MUX_3") (pin "11") (pinfunction "3A_11") (pintype "input"))
      (node (ref "U_FLAGS_MUX_3") (pin "13") (pinfunction "4B_13") (pintype "input"))
      (node (ref "U_FLAGS_MUX_3") (pin "14") (pinfunction "4A_14") (pintype "input"))
      (node (ref "U_FLAGS_MUX_3") (pin "15") (pinfunction "G_15") (pintype "input"))
      (node (ref "U_FLAGS_MUX_3") (pin "5") (pinfunction "2A_5") (pintype "input"))
      (node (ref "U_FLAGS_MUX_3") (pin "6") (pinfunction "2B_6") (pintype "input"))
    )
    (net (code "40") (name "INT_PENDING") (class "Default")
      (node (ref "2AND_0") (pin "13") (pinfunction "I1_13") (pintype "input"))
      (node (ref "2OR_1") (pin "10") (pinfunction "I1_10") (pintype "input"))
      (node (ref "3AND_0") (pin "3") (pinfunction "I0_3") (pintype "input"))
    )
    (net (code "41") (name "IR_0") (class "Default")
      (node (ref "IR_L") (pin "2") (pinfunction "1Q_2") (pintype "output"))
      (node (ref "U_ADDR_MUX_4") (pin "3") (pinfunction "D1_3") (pintype "input"))
    )
    (net (code "42") (name "IR_1") (class "Default")
      (node (ref "IR_L") (pin "5") (pinfunction "2Q_5") (pintype "output"))
      (node (ref "U_ADDR_MUX_5") (pin "3") (pinfunction "D1_3") (pintype "input"))
    )
    (net (code "43") (name "IR_2") (class "Default")
      (node (ref "IR_L") (pin "6") (pinfunction "3Q_6") (pintype "output"))
      (node (ref "U_ADDR_MUX_6") (pin "3") (pinfunction "D1_3") (pintype "input"))
    )
    (net (code "44") (name "IR_3") (class "Default")
      (node (ref "IR_L") (pin "9") (pinfunction "4Q_9") (pintype "output"))
      (node (ref "U_ADDR_MUX_7") (pin "3") (pinfunction "D1_3") (pintype "input"))
    )
    (net (code "45") (name "IR_4") (class "Default")
      (node (ref "IR_L") (pin "12") (pinfunction "5Q_12") (pintype "output"))
      (node (ref "U_ADDR_MUX_8") (pin "3") (pinfunction "D1_3") (pintype "input"))
    )
    (net (code "46") (name "IR_5") (class "Default")
      (node (ref "IR_L") (pin "15") (pinfunction "6Q_15") (pintype "output"))
      (node (ref "U_ADDR_MUX_9") (pin "3") (pinfunction "D1_3") (pintype "input"))
    )
    (net (code "47") (name "IR_6") (class "Default")
      (node (ref "IR_L") (pin "16") (pinfunction "7Q_16") (pintype "output"))
      (node (ref "U_ADDR_MUX_10") (pin "3") (pinfunction "D1_3") (pintype "input"))
    )
    (net (code "48") (name "IR_7") (class "Default")
      (node (ref "IR_L") (pin "19") (pinfunction "8Q_19") (pintype "output"))
      (node (ref "U_ADDR_MUX_11") (pin "3") (pinfunction "D1_3") (pintype "input"))
    )
    (net (code "49") (name "IR_8") (class "Default")
      (node (ref "IR_H") (pin "2") (pinfunction "1Q_2") (pintype "output"))
      (node (ref "U_ADDR_MUX_12") (pin "3") (pinfunction "D1_3") (pintype "input"))
    )
    (net (code "50") (name "IR_9") (class "Default")
      (node (ref "IR_H") (pin "5") (pinfunction "2Q_5") (pintype "output"))
      (node (ref "U_ADDR_MUX_13") (pin "3") (pinfunction "D1_3") (pintype "input"))
    )
    (net (code "51") (name "IR_10") (class "Default")
      (node (ref "IR_H") (pin "6") (pinfunction "3Q_6") (pintype "output"))
      (node (ref "U_ADDR_MUX_14") (pin "3") (pinfunction "D1_3") (pintype "input"))
    )
    (net (code "52") (name "IR_11") (class "Default")
      (node (ref "IR_H") (pin "9") (pinfunction "4Q_9") (pintype "output"))
      (node (ref "U_ADDR_MUX_15") (pin "3") (pinfunction "D1_3") (pintype "input"))
    )
    (net (code "53") (name "IR_H_WRT") (class "Default")
      (node (ref "IR_H") (pin "1") (pinfunction "G_1") (pintype "input"))
    )
    (net (code "54") (name "IR_L_WRT") (class "Default")
      (node (ref "IR_L") (pin "1") (pinfunction "G_1") (pintype "input"))
    )
    (net (code "55") (name "MUX_A") (class "Default")
      (node (ref "2AND_0") (pin "8") (pinfunction "O_8") (pintype "output"))
      (node (ref "U_ADDR_MUX_0") (pin "11") (pinfunction "A_11") (pintype "input"))
      (node (ref "U_ADDR_MUX_1") (pin "11") (pinfunction "A_11") (pintype "input"))
      (node (ref "U_ADDR_MUX_10") (pin "11") (pinfunction "A_11") (pintype "input"))
      (node (ref "U_ADDR_MUX_11") (pin "11") (pinfunction "A_11") (pintype "input"))
      (node (ref "U_ADDR_MUX_12") (pin "11") (pinfunction "A_11") (pintype "input"))
      (node (ref "U_ADDR_MUX_13") (pin "11") (pinfunction "A_11") (pintype "input"))
      (node (ref "U_ADDR_MUX_14") (pin "11") (pinfunction "A_11") (pintype "input"))
      (node (ref "U_ADDR_MUX_15") (pin "11") (pinfunction "A_11") (pintype "input"))
      (node (ref "U_ADDR_MUX_2") (pin "11") (pinfunction "A_11") (pintype "input"))
      (node (ref "U_ADDR_MUX_3") (pin "11") (pinfunction "A_11") (pintype "input"))
      (node (ref "U_ADDR_MUX_4") (pin "11") (pinfunction "A_11") (pintype "input"))
      (node (ref "U_ADDR_MUX_5") (pin "11") (pinfunction "A_11") (pintype "input"))
      (node (ref "U_ADDR_MUX_6") (pin "11") (pinfunction "A_11") (pintype "input"))
      (node (ref "U_ADDR_MUX_7") (pin "11") (pinfunction "A_11") (pintype "input"))
      (node (ref "U_ADDR_MUX_8") (pin "11") (pinfunction "A_11") (pintype "input"))
      (node (ref "U_ADDR_MUX_9") (pin "11") (pinfunction "A_11") (pintype "input"))
    )
    (net (code "56") (name "MUX_B") (class "Default")
      (node (ref "3AND_0") (pin "8") (pinfunction "O_8") (pintype "output"))
      (node (ref "U_ADDR_MUX_0") (pin "10") (pinfunction "B_10") (pintype "input"))
      (node (ref "U_ADDR_MUX_1") (pin "10") (pinfunction "B_10") (pintype "input"))
      (node (ref "U_ADDR_MUX_10") (pin "10") (pinfunction "B_10") (pintype "input"))
      (node (ref "U_ADDR_MUX_11") (pin "10") (pinfunction "B_10") (pintype "input"))
      (node (ref "U_ADDR_MUX_12") (pin "10") (pinfunction "B_10") (pintype "input"))
      (node (ref "U_ADDR_MUX_13") (pin "10") (pinfunction "B_10") (pintype "input"))
      (node (ref "U_ADDR_MUX_14") (pin "10") (pinfunction "B_10") (pintype "input"))
      (node (ref "U_ADDR_MUX_15") (pin "10") (pinfunction "B_10") (pintype "input"))
      (node (ref "U_ADDR_MUX_2") (pin "10") (pinfunction "B_10") (pintype "input"))
      (node (ref "U_ADDR_MUX_3") (pin "10") (pinfunction "B_10") (pintype "input"))
      (node (ref "U_ADDR_MUX_4") (pin "10") (pinfunction "B_10") (pintype "input"))
      (node (ref "U_ADDR_MUX_5") (pin "10") (pinfunction "B_10") (pintype "input"))
      (node (ref "U_ADDR_MUX_6") (pin "10") (pinfunction "B_10") (pintype "input"))
      (node (ref "U_ADDR_MUX_7") (pin "10") (pinfunction "B_10") (pintype "input"))
      (node (ref "U_ADDR_MUX_8") (pin "10") (pinfunction "B_10") (pintype "input"))
      (node (ref "U_ADDR_MUX_9") (pin "10") (pinfunction "B_10") (pintype "input"))
    )
    (net (code "57") (name "MUX_C") (class "Default")
      (node (ref "NOT_1") (pin "2") (pinfunction "O_2") (pintype "output"))
      (node (ref "U_ADDR_MUX_0") (pin "9") (pinfunction "C_9") (pintype "input"))
      (node (ref "U_ADDR_MUX_1") (pin "9") (pinfunction "C_9") (pintype "input"))
      (node (ref "U_ADDR_MUX_10") (pin "9") (pinfunction "C_9") (pintype "input"))
      (node (ref "U_ADDR_MUX_11") (pin "9") (pinfunction "C_9") (pintype "input"))
      (node (ref "U_ADDR_MUX_12") (pin "9") (pinfunction "C_9") (pintype "input"))
      (node (ref "U_ADDR_MUX_13") (pin "9") (pinfunction "C_9") (pintype "input"))
      (node (ref "U_ADDR_MUX_14") (pin "9") (pinfunction "C_9") (pintype "input"))
      (node (ref "U_ADDR_MUX_15") (pin "9") (pinfunction "C_9") (pintype "input"))
      (node (ref "U_ADDR_MUX_2") (pin "9") (pinfunction "C_9") (pintype "input"))
      (node (ref "U_ADDR_MUX_3") (pin "9") (pinfunction "C_9") (pintype "input"))
      (node (ref "U_ADDR_MUX_4") (pin "9") (pinfunction "C_9") (pintype "input"))
      (node (ref "U_ADDR_MUX_5") (pin "9") (pinfunction "C_9") (pintype "input"))
      (node (ref "U_ADDR_MUX_6") (pin "9") (pinfunction "C_9") (pintype "input"))
      (node (ref "U_ADDR_MUX_7") (pin "9") (pinfunction "C_9") (pintype "input"))
      (node (ref "U_ADDR_MUX_8") (pin "9") (pinfunction "C_9") (pintype "input"))
      (node (ref "U_ADDR_MUX_9") (pin "9") (pinfunction "C_9") (pintype "input"))
    )
    (net (code "58") (name "Net-(2AND_0A-O)") (class "Default")
      (node (ref "2AND_0") (pin "3") (pinfunction "O_3") (pintype "output"))
      (node (ref "U_FLAGS_MUX_0") (pin "4") (pinfunction "1C2_4") (pintype "input"))
    )
    (net (code "59") (name "Net-(2AND_0B-I0)") (class "Default")
      (node (ref "2AND_0") (pin "4") (pinfunction "I0_4") (pintype "input"))
      (node (ref "2OR_0") (pin "3") (pinfunction "O_3") (pintype "output"))
    )
    (net (code "60") (name "Net-(2AND_0B-I1)") (class "Default")
      (node (ref "2AND_0") (pin "5") (pinfunction "I1_5") (pintype "input"))
      (node (ref "3AND_0") (pin "10") (pinfunction "I1_10") (pintype "input"))
      (node (ref "4NAND_0") (pin "2") (pinfunction "I1_2") (pintype "input"))
      (node (ref "NOT_0") (pin "8") (pinfunction "O_8") (pintype "output"))
    )
    (net (code "61") (name "Net-(2AND_0B-O)") (class "Default")
      (node (ref "2AND_0") (pin "6") (pinfunction "O_6") (pintype "output"))
      (node (ref "2OR_0") (pin "4") (pinfunction "I0_4") (pintype "input"))
    )
    (net (code "62") (name "Net-(2AND_0C-I0)") (class "Default")
      (node (ref "2AND_0") (pin "9") (pinfunction "I0_9") (pintype "input"))
      (node (ref "2OR_0") (pin "6") (pinfunction "O_6") (pintype "output"))
    )
    (net (code "63") (name "Net-(2AND_0D-I0)") (class "Default")
      (node (ref "2AND_0") (pin "12") (pinfunction "I0_12") (pintype "input"))
      (node (ref "3AND_0") (pin "4") (pinfunction "I1_4") (pintype "input"))
      (node (ref "NOT_0") (pin "12") (pinfunction "O_12") (pintype "output"))
    )
    (net (code "64") (name "Net-(2AND_0D-O)") (class "Default")
      (node (ref "2AND_0") (pin "11") (pinfunction "O_11") (pintype "output"))
      (node (ref "2OR_0") (pin "10") (pinfunction "I1_10") (pintype "input"))
    )
    (net (code "65") (name "Net-(2AND_1A-O)") (class "Default")
      (node (ref "2AND_1") (pin "3") (pinfunction "O_3") (pintype "output"))
      (node (ref "COND_MUX_0") (pin "3") (pinfunction "1C3_3") (pintype "input"))
    )
    (net (code "66") (name "Net-(2OR_0A-I1)") (class "Default")
      (node (ref "2OR_0") (pin "2") (pinfunction "I1_2") (pintype "input"))
      (node (ref "3AND_0") (pin "6") (pinfunction "O_6") (pintype "output"))
    )
    (net (code "67") (name "Net-(2OR_0C-O)") (class "Default")
      (node (ref "2OR_0") (pin "8") (pinfunction "O_8") (pintype "output"))
      (node (ref "4NAND_0") (pin "5") (pinfunction "I3_5") (pintype "input"))
    )
    (net (code "68") (name "Net-(2OR_0D-I0)") (class "Default")
      (node (ref "2OR_0") (pin "12") (pinfunction "I0_12") (pintype "input"))
      (node (ref "2XOR_0") (pin "3") (pinfunction "O_3") (pintype "output"))
      (node (ref "COND_MUX_2") (pin "13") (pinfunction "D6_13") (pintype "input"))
    )
    (net (code "69") (name "Net-(2OR_0D-I1)") (class "Default")
      (node (ref "2OR_0") (pin "13") (pinfunction "I1_13") (pintype "input"))
      (node (ref "2OR_1") (pin "2") (pinfunction "I1_2") (pintype "input"))
      (node (ref "COND_MUX_0") (pin "7") (pinfunction "1Y_7") (pintype "output"))
      (node (ref "COND_MUX_2") (pin "4") (pinfunction "D0_4") (pintype "input"))
    )
    (net (code "70") (name "Net-(2OR_0D-O)") (class "Default")
      (node (ref "2OR_0") (pin "11") (pinfunction "O_11") (pintype "output"))
      (node (ref "COND_MUX_2") (pin "12") (pinfunction "D7_12") (pintype "input"))
    )
    (net (code "71") (name "Net-(2OR_1A-I0)") (class "Default")
      (node (ref "2OR_1") (pin "1") (pinfunction "I0_1") (pintype "input"))
      (node (ref "COND_MUX_0") (pin "9") (pinfunction "2Y_9") (pintype "output"))
      (node (ref "COND_MUX_2") (pin "15") (pinfunction "D4_15") (pintype "input"))
      (node (ref "COND_MUX_2") (pin "3") (pinfunction "D1_3") (pintype "input"))
    )
    (net (code "72") (name "Net-(2OR_1A-O)") (class "Default")
      (node (ref "2OR_1") (pin "3") (pinfunction "O_3") (pintype "output"))
      (node (ref "COND_MUX_2") (pin "14") (pinfunction "D5_14") (pintype "input"))
    )
    (net (code "73") (name "Net-(2OR_1B-I0)") (class "Default")
      (node (ref "2OR_1") (pin "4") (pinfunction "I0_4") (pintype "input"))
      (node (ref "NOT_1") (pin "4") (pinfunction "O_4") (pintype "output"))
    )
    (net (code "74") (name "Net-(2OR_1B-O)") (class "Default")
      (node (ref "2OR_1") (pin "6") (pinfunction "O_6") (pintype "output"))
      (node (ref "3AND_0") (pin "11") (pinfunction "I2_11") (pintype "input"))
    )
    (net (code "75") (name "Net-(2OR_1C-O)") (class "Default")
      (node (ref "2OR_1") (pin "8") (pinfunction "O_8") (pintype "output"))
      (node (ref "NOT_1") (pin "3") (pinfunction "I_3") (pintype "input"))
    )
    (net (code "76") (name "Net-(2XOR_0A-I0)") (class "Default")
      (node (ref "2XOR_0") (pin "1") (pinfunction "I0_1") (pintype "input"))
      (node (ref "COND_MUX_1") (pin "7") (pinfunction "1Y_7") (pintype "output"))
      (node (ref "COND_MUX_2") (pin "2") (pinfunction "D2_2") (pintype "input"))
    )
    (net (code "77") (name "Net-(2XOR_0A-I1)") (class "Default")
      (node (ref "2XOR_0") (pin "2") (pinfunction "I1_2") (pintype "input"))
      (node (ref "COND_MUX_1") (pin "9") (pinfunction "2Y_9") (pintype "output"))
      (node (ref "COND_MUX_2") (pin "1") (pinfunction "D3_1") (pintype "input"))
    )
    (net (code "78") (name "Net-(3AND_0A-I1)") (class "Default")
      (node (ref "3AND_0") (pin "2") (pinfunction "I1_2") (pintype "input"))
      (node (ref "NOT_0") (pin "2") (pinfunction "O_2") (pintype "output"))
    )
    (net (code "79") (name "Net-(3AND_0A-I2)") (class "Default")
      (node (ref "3AND_0") (pin "13") (pinfunction "I2_13") (pintype "input"))
      (node (ref "NOT_0") (pin "4") (pinfunction "O_4") (pintype "output"))
    )
    (net (code "80") (name "Net-(3AND_0A-O)") (class "Default")
      (node (ref "3AND_0") (pin "12") (pinfunction "O_12") (pintype "output"))
      (node (ref "NOT_0") (pin "5") (pinfunction "I_5") (pintype "input"))
    )
    (net (code "81") (name "Net-(3AND_0B-I2)") (class "Default")
      (node (ref "3AND_0") (pin "5") (pinfunction "I2_5") (pintype "input"))
      (node (ref "4NAND_0") (pin "4") (pinfunction "I2_4") (pintype "input"))
      (node (ref "NOT_0") (pin "10") (pinfunction "O_10") (pintype "output"))
    )
    (net (code "82") (name "Net-(4NAND_0A-O)") (class "Default")
      (node (ref "4NAND_0") (pin "6") (pinfunction "O_6") (pintype "output"))
      (node (ref "NOT_1") (pin "1") (pinfunction "I_1") (pintype "input"))
    )
    (net (code "83") (name "Net-(IR_HA-CLK)") (class "Default")
      (node (ref "IR_H") (pin "11") (pinfunction "CLK_11") (pintype "input"))
      (node (ref "IR_L") (pin "11") (pinfunction "CLK_11") (pintype "input"))
    )
    (net (code "84") (name "Net-(NOT_0C-O)") (class "Default")
      (node (ref "NOT_0") (pin "6") (pinfunction "O_6") (pintype "output"))
      (node (ref "U_ADDER_MUX_0") (pin "1") (pinfunction "~{A}/B_1") (pintype "input"))
      (node (ref "U_ADDER_MUX_1") (pin "1") (pinfunction "~{A}/B_1") (pintype "input"))
      (node (ref "U_ADDER_MUX_2") (pin "1") (pinfunction "~{A}/B_1") (pintype "input"))
      (node (ref "U_ADDER_MUX_3") (pin "1") (pinfunction "~{A}/B_1") (pintype "input"))
    )
    (net (code "85") (name "Net-(U_ADDER_0A-B1)") (class "Default")
      (node (ref "U_ADDER_0") (pin "6") (pinfunction "B1_6") (pintype "input"))
      (node (ref "U_ADDER_MUX_0") (pin "4") (pinfunction "1Y_4") (pintype "tri_state"))
    )
    (net (code "86") (name "Net-(U_ADDER_0A-B2)") (class "Default")
      (node (ref "U_ADDER_0") (pin "2") (pinfunction "B2_2") (pintype "input"))
      (node (ref "U_ADDER_MUX_0") (pin "7") (pinfunction "2Y_7") (pintype "tri_state"))
    )
    (net (code "87") (name "Net-(U_ADDER_0A-B3)") (class "Default")
      (node (ref "U_ADDER_0") (pin "15") (pinfunction "B3_15") (pintype "input"))
      (node (ref "U_ADDER_MUX_0") (pin "9") (pinfunction "3Y_9") (pintype "tri_state"))
    )
    (net (code "88") (name "Net-(U_ADDER_0A-B4)") (class "Default")
      (node (ref "U_ADDER_0") (pin "11") (pinfunction "B4_11") (pintype "input"))
      (node (ref "U_ADDER_MUX_0") (pin "12") (pinfunction "4Y_12") (pintype "tri_state"))
    )
    (net (code "89") (name "Net-(U_ADDER_0A-C4)") (class "Default")
      (node (ref "U_ADDER_0") (pin "9") (pinfunction "C4_9") (pintype "output"))
      (node (ref "U_ADDER_1") (pin "7") (pinfunction "C0_7") (pintype "input"))
    )
    (net (code "90") (name "Net-(U_ADDER_1A-B1)") (class "Default")
      (node (ref "U_ADDER_1") (pin "6") (pinfunction "B1_6") (pintype "input"))
      (node (ref "U_ADDER_MUX_1") (pin "4") (pinfunction "1Y_4") (pintype "tri_state"))
    )
    (net (code "91") (name "Net-(U_ADDER_1A-B2)") (class "Default")
      (node (ref "U_ADDER_1") (pin "2") (pinfunction "B2_2") (pintype "input"))
      (node (ref "U_ADDER_MUX_1") (pin "7") (pinfunction "2Y_7") (pintype "tri_state"))
    )
    (net (code "92") (name "Net-(U_ADDER_1A-B3)") (class "Default")
      (node (ref "U_ADDER_1") (pin "15") (pinfunction "B3_15") (pintype "input"))
      (node (ref "U_ADDER_MUX_1") (pin "9") (pinfunction "3Y_9") (pintype "tri_state"))
    )
    (net (code "93") (name "Net-(U_ADDER_1A-B4)") (class "Default")
      (node (ref "U_ADDER_1") (pin "11") (pinfunction "B4_11") (pintype "input"))
      (node (ref "U_ADDER_MUX_1") (pin "12") (pinfunction "4Y_12") (pintype "tri_state"))
    )
    (net (code "94") (name "Net-(U_ADDER_1A-C4)") (class "Default")
      (node (ref "U_ADDER_1") (pin "9") (pinfunction "C4_9") (pintype "output"))
      (node (ref "U_ADDER_2") (pin "7") (pinfunction "C0_7") (pintype "input"))
    )
    (net (code "95") (name "Net-(U_ADDER_2A-B1)") (class "Default")
      (node (ref "U_ADDER_2") (pin "6") (pinfunction "B1_6") (pintype "input"))
      (node (ref "U_ADDER_MUX_2") (pin "4") (pinfunction "1Y_4") (pintype "tri_state"))
    )
    (net (code "96") (name "Net-(U_ADDER_2A-B2)") (class "Default")
      (node (ref "U_ADDER_2") (pin "2") (pinfunction "B2_2") (pintype "input"))
      (node (ref "U_ADDER_MUX_2") (pin "7") (pinfunction "2Y_7") (pintype "tri_state"))
    )
    (net (code "97") (name "Net-(U_ADDER_2A-B3)") (class "Default")
      (node (ref "U_ADDER_2") (pin "15") (pinfunction "B3_15") (pintype "input"))
      (node (ref "U_ADDER_MUX_2") (pin "9") (pinfunction "3Y_9") (pintype "tri_state"))
    )
    (net (code "98") (name "Net-(U_ADDER_2A-B4)") (class "Default")
      (node (ref "U_ADDER_2") (pin "11") (pinfunction "B4_11") (pintype "input"))
      (node (ref "U_ADDER_MUX_2") (pin "12") (pinfunction "4Y_12") (pintype "tri_state"))
    )
    (net (code "99") (name "Net-(U_ADDER_2A-C4)") (class "Default")
      (node (ref "U_ADDER_2") (pin "9") (pinfunction "C4_9") (pintype "output"))
      (node (ref "U_ADDER_3") (pin "7") (pinfunction "C0_7") (pintype "input"))
    )
    (net (code "100") (name "Net-(U_ADDER_3A-B1)") (class "Default")
      (node (ref "U_ADDER_3") (pin "6") (pinfunction "B1_6") (pintype "input"))
      (node (ref "U_ADDER_MUX_3") (pin "4") (pinfunction "1Y_4") (pintype "tri_state"))
    )
    (net (code "101") (name "Net-(U_ADDER_3A-B2)") (class "Default")
      (node (ref "U_ADDER_3") (pin "2") (pinfunction "B2_2") (pintype "input"))
      (node (ref "U_ADDER_MUX_3") (pin "7") (pinfunction "2Y_7") (pintype "tri_state"))
    )
    (net (code "102") (name "Net-(U_ADDER_3A-B3)") (class "Default")
      (node (ref "U_ADDER_3") (pin "15") (pinfunction "B3_15") (pintype "input"))
      (node (ref "U_ADDER_MUX_3") (pin "9") (pinfunction "3Y_9") (pintype "tri_state"))
    )
    (net (code "103") (name "Net-(U_ADDER_3A-B4)") (class "Default")
      (node (ref "U_ADDER_3") (pin "11") (pinfunction "B4_11") (pintype "input"))
      (node (ref "U_ADDER_MUX_3") (pin "12") (pinfunction "4Y_12") (pintype "tri_state"))
    )
    (net (code "104") (name "Net-(U_ADDR_HA-CLK)") (class "Default")
      (node (ref "U_ADDR_H") (pin "11") (pinfunction "CLK_11") (pintype "input"))
      (node (ref "U_ADDR_L") (pin "11") (pinfunction "CLK_11") (pintype "input"))
    )
    (net (code "105") (name "Net-(U_ADDR_HA-D1)") (class "Default")
      (node (ref "U_ADDR_H") (pin "3") (pinfunction "D1_3") (pintype "input"))
      (node (ref "U_ADDR_MUX_8") (pin "5") (pinfunction "Y_5") (pintype "output"))
    )
    (net (code "106") (name "Net-(U_ADDR_HA-D2)") (class "Default")
      (node (ref "U_ADDR_H") (pin "4") (pinfunction "D2_4") (pintype "input"))
      (node (ref "U_ADDR_MUX_9") (pin "5") (pinfunction "Y_5") (pintype "output"))
    )
    (net (code "107") (name "Net-(U_ADDR_HA-D3)") (class "Default")
      (node (ref "U_ADDR_H") (pin "7") (pinfunction "D3_7") (pintype "input"))
      (node (ref "U_ADDR_MUX_10") (pin "5") (pinfunction "Y_5") (pintype "output"))
    )
    (net (code "108") (name "Net-(U_ADDR_HA-D4)") (class "Default")
      (node (ref "U_ADDR_H") (pin "8") (pinfunction "D4_8") (pintype "input"))
      (node (ref "U_ADDR_MUX_11") (pin "5") (pinfunction "Y_5") (pintype "output"))
    )
    (net (code "109") (name "Net-(U_ADDR_HA-D5)") (class "Default")
      (node (ref "U_ADDR_H") (pin "13") (pinfunction "D5_13") (pintype "input"))
      (node (ref "U_ADDR_MUX_12") (pin "5") (pinfunction "Y_5") (pintype "output"))
    )
    (net (code "110") (name "Net-(U_ADDR_HA-D6)") (class "Default")
      (node (ref "U_ADDR_H") (pin "14") (pinfunction "D6_14") (pintype "input"))
      (node (ref "U_ADDR_MUX_13") (pin "5") (pinfunction "Y_5") (pintype "output"))
    )
    (net (code "111") (name "Net-(U_ADDR_HA-D7)") (class "Default")
      (node (ref "U_ADDR_H") (pin "17") (pinfunction "D7_17") (pintype "input"))
      (node (ref "U_ADDR_MUX_14") (pin "5") (pinfunction "Y_5") (pintype "output"))
    )
    (net (code "112") (name "Net-(U_ADDR_HA-D8)") (class "Default")
      (node (ref "U_ADDR_H") (pin "18") (pinfunction "D8_18") (pintype "input"))
      (node (ref "U_ADDR_MUX_15") (pin "5") (pinfunction "Y_5") (pintype "output"))
    )
    (net (code "113") (name "Net-(U_ADDR_LA-D1)") (class "Default")
      (node (ref "U_ADDR_L") (pin "3") (pinfunction "D1_3") (pintype "input"))
      (node (ref "U_ADDR_MUX_0") (pin "5") (pinfunction "Y_5") (pintype "output"))
    )
    (net (code "114") (name "Net-(U_ADDR_LA-D2)") (class "Default")
      (node (ref "U_ADDR_L") (pin "4") (pinfunction "D2_4") (pintype "input"))
      (node (ref "U_ADDR_MUX_1") (pin "5") (pinfunction "Y_5") (pintype "output"))
    )
    (net (code "115") (name "Net-(U_ADDR_LA-D3)") (class "Default")
      (node (ref "U_ADDR_L") (pin "7") (pinfunction "D3_7") (pintype "input"))
      (node (ref "U_ADDR_MUX_2") (pin "5") (pinfunction "Y_5") (pintype "output"))
    )
    (net (code "116") (name "Net-(U_ADDR_LA-D4)") (class "Default")
      (node (ref "U_ADDR_L") (pin "8") (pinfunction "D4_8") (pintype "input"))
      (node (ref "U_ADDR_MUX_3") (pin "5") (pinfunction "Y_5") (pintype "output"))
    )
    (net (code "117") (name "Net-(U_ADDR_LA-D5)") (class "Default")
      (node (ref "U_ADDR_L") (pin "13") (pinfunction "D5_13") (pintype "input"))
      (node (ref "U_ADDR_MUX_4") (pin "5") (pinfunction "Y_5") (pintype "output"))
    )
    (net (code "118") (name "Net-(U_ADDR_LA-D6)") (class "Default")
      (node (ref "U_ADDR_L") (pin "14") (pinfunction "D6_14") (pintype "input"))
      (node (ref "U_ADDR_MUX_5") (pin "5") (pinfunction "Y_5") (pintype "output"))
    )
    (net (code "119") (name "Net-(U_ADDR_LA-D7)") (class "Default")
      (node (ref "U_ADDR_L") (pin "17") (pinfunction "D7_17") (pintype "input"))
      (node (ref "U_ADDR_MUX_6") (pin "5") (pinfunction "Y_5") (pintype "output"))
    )
    (net (code "120") (name "Net-(U_ADDR_LA-D8)") (class "Default")
      (node (ref "U_ADDR_L") (pin "18") (pinfunction "D8_18") (pintype "input"))
      (node (ref "U_ADDR_MUX_7") (pin "5") (pinfunction "Y_5") (pintype "output"))
    )
    (net (code "121") (name "Net-(U_FLAGSA-D1)") (class "Default")
      (node (ref "U_FLAGS") (pin "3") (pinfunction "D1_3") (pintype "input"))
      (node (ref "U_FLAGS_MUX_0") (pin "7") (pinfunction "1Y_7") (pintype "output"))
    )
    (net (code "122") (name "Net-(U_FLAGSA-D2)") (class "Default")
      (node (ref "U_FLAGS") (pin "4") (pinfunction "D2_4") (pintype "input"))
      (node (ref "U_FLAGS_MUX_1") (pin "7") (pinfunction "1Y_7") (pintype "output"))
    )
    (net (code "123") (name "Net-(U_FLAGSA-D3)") (class "Default")
      (node (ref "U_FLAGS") (pin "7") (pinfunction "D3_7") (pintype "input"))
      (node (ref "U_FLAGS_MUX_2") (pin "4") (pinfunction "1Y_4") (pintype "tri_state"))
    )
    (net (code "124") (name "Net-(U_FLAGSA-D4)") (class "Default")
      (node (ref "U_FLAGS") (pin "8") (pinfunction "D4_8") (pintype "input"))
      (node (ref "U_FLAGS_MUX_3") (pin "4") (pinfunction "1Y_4") (pintype "tri_state"))
    )
    (net (code "125") (name "OF") (class "Default")
      (node (ref "COND_MUX_1") (pin "10") (pinfunction "2C0_10") (pintype "input"))
    )
    (net (code "126") (name "OF_FROM_ALU") (class "Default")
      (node (ref "COND_MUX_1") (pin "12") (pinfunction "2C2_12") (pintype "input"))
      (node (ref "U_FLAGS_MUX_3") (pin "3") (pinfunction "1B_3") (pintype "input"))
    )
    (net (code "127") (name "SF") (class "Default")
      (node (ref "COND_MUX_1") (pin "6") (pinfunction "1C0_6") (pintype "input"))
    )
    (net (code "128") (name "SF_FROM_ALU") (class "Default")
      (node (ref "COND_MUX_1") (pin "4") (pinfunction "1C2_4") (pintype "input"))
      (node (ref "U_FLAGS_MUX_2") (pin "3") (pinfunction "1B_3") (pintype "input"))
    )
    (net (code "129") (name "TRAP_PENDING") (class "Default")
      (node (ref "2OR_0") (pin "1") (pinfunction "I0_1") (pintype "input"))
      (node (ref "2OR_1") (pin "5") (pinfunction "I1_5") (pintype "input"))
      (node (ref "NOT_0") (pin "11") (pinfunction "I_11") (pintype "input"))
    )
    (net (code "130") (name "TYP0") (class "Default")
      (node (ref "2OR_0") (pin "5") (pinfunction "I1_5") (pintype "input"))
      (node (ref "3AND_0") (pin "1") (pinfunction "I0_1") (pintype "input"))
      (node (ref "NOT_0") (pin "9") (pinfunction "I_9") (pintype "input"))
    )
    (net (code "131") (name "TYP1") (class "Default")
      (node (ref "2AND_0") (pin "10") (pinfunction "I1_10") (pintype "input"))
      (node (ref "3AND_0") (pin "9") (pinfunction "I0_9") (pintype "input"))
      (node (ref "4NAND_0") (pin "1") (pinfunction "I0_1") (pintype "input"))
      (node (ref "NOT_0") (pin "1") (pinfunction "I_1") (pintype "input"))
    )
    (net (code "132") (name "U_ADDER_0") (class "Default")
      (node (ref "U_ADDER_0") (pin "4") (pinfunction "S1_4") (pintype "output"))
      (node (ref "U_ADDR_MUX_0") (pin "4") (pinfunction "D0_4") (pintype "input"))
    )
    (net (code "133") (name "U_ADDER_1") (class "Default")
      (node (ref "U_ADDER_0") (pin "1") (pinfunction "S2_1") (pintype "output"))
      (node (ref "U_ADDR_MUX_1") (pin "4") (pinfunction "D0_4") (pintype "input"))
    )
    (net (code "134") (name "U_ADDER_2") (class "Default")
      (node (ref "U_ADDER_0") (pin "13") (pinfunction "S3_13") (pintype "output"))
      (node (ref "U_ADDR_MUX_2") (pin "4") (pinfunction "D0_4") (pintype "input"))
    )
    (net (code "135") (name "U_ADDER_3") (class "Default")
      (node (ref "U_ADDER_0") (pin "10") (pinfunction "S4_10") (pintype "output"))
      (node (ref "U_ADDR_MUX_3") (pin "4") (pinfunction "D0_4") (pintype "input"))
    )
    (net (code "136") (name "U_ADDER_4") (class "Default")
      (node (ref "U_ADDER_1") (pin "4") (pinfunction "S1_4") (pintype "output"))
      (node (ref "U_ADDR_MUX_4") (pin "4") (pinfunction "D0_4") (pintype "input"))
    )
    (net (code "137") (name "U_ADDER_5") (class "Default")
      (node (ref "U_ADDER_1") (pin "1") (pinfunction "S2_1") (pintype "output"))
      (node (ref "U_ADDR_MUX_5") (pin "4") (pinfunction "D0_4") (pintype "input"))
    )
    (net (code "138") (name "U_ADDER_6") (class "Default")
      (node (ref "U_ADDER_1") (pin "13") (pinfunction "S3_13") (pintype "output"))
      (node (ref "U_ADDR_MUX_6") (pin "4") (pinfunction "D0_4") (pintype "input"))
    )
    (net (code "139") (name "U_ADDER_7") (class "Default")
      (node (ref "U_ADDER_1") (pin "10") (pinfunction "S4_10") (pintype "output"))
      (node (ref "U_ADDR_MUX_7") (pin "4") (pinfunction "D0_4") (pintype "input"))
    )
    (net (code "140") (name "U_ADDER_8") (class "Default")
      (node (ref "U_ADDER_2") (pin "4") (pinfunction "S1_4") (pintype "output"))
      (node (ref "U_ADDR_MUX_8") (pin "4") (pinfunction "D0_4") (pintype "input"))
    )
    (net (code "141") (name "U_ADDER_9") (class "Default")
      (node (ref "U_ADDER_2") (pin "1") (pinfunction "S2_1") (pintype "output"))
      (node (ref "U_ADDR_MUX_9") (pin "4") (pinfunction "D0_4") (pintype "input"))
    )
    (net (code "142") (name "U_ADDER_10") (class "Default")
      (node (ref "U_ADDER_2") (pin "13") (pinfunction "S3_13") (pintype "output"))
      (node (ref "U_ADDR_MUX_10") (pin "4") (pinfunction "D0_4") (pintype "input"))
    )
    (net (code "143") (name "U_ADDER_11") (class "Default")
      (node (ref "U_ADDER_2") (pin "10") (pinfunction "S4_10") (pintype "output"))
      (node (ref "U_ADDR_MUX_11") (pin "4") (pinfunction "D0_4") (pintype "input"))
    )
    (net (code "144") (name "U_ADDER_12") (class "Default")
      (node (ref "U_ADDER_3") (pin "4") (pinfunction "S1_4") (pintype "output"))
      (node (ref "U_ADDR_MUX_12") (pin "4") (pinfunction "D0_4") (pintype "input"))
    )
    (net (code "145") (name "U_ADDER_13") (class "Default")
      (node (ref "U_ADDER_3") (pin "1") (pinfunction "S2_1") (pintype "output"))
      (node (ref "U_ADDR_MUX_13") (pin "4") (pinfunction "D0_4") (pintype "input"))
    )
    (net (code "146") (name "U_ADDER_14") (class "Default")
      (node (ref "U_ADDER_3") (pin "13") (pinfunction "S3_13") (pintype "output"))
      (node (ref "U_ADDR_MUX_14") (pin "4") (pinfunction "D0_4") (pintype "input"))
    )
    (net (code "147") (name "U_ADDER_15") (class "Default")
      (node (ref "U_ADDER_3") (pin "10") (pinfunction "S4_10") (pintype "output"))
      (node (ref "U_ADDR_MUX_15") (pin "4") (pinfunction "D0_4") (pintype "input"))
    )
    (net (code "148") (name "U_CF") (class "Default")
      (node (ref "COND_MUX_0") (pin "11") (pinfunction "2C1_11") (pintype "input"))
      (node (ref "U_FLAGS") (pin "5") (pinfunction "Q2_5") (pintype "output"))
      (node (ref "U_FLAGS_MUX_1") (pin "6") (pinfunction "1C0_6") (pintype "input"))
    )
    (net (code "149") (name "U_CF_IN_SRC_0") (class "Default")
      (node (ref "U_FLAGS_MUX_1") (pin "14") (pinfunction "A_14") (pintype "input"))
    )
    (net (code "150") (name "U_CF_IN_SRC_1") (class "Default")
      (node (ref "U_FLAGS_MUX_1") (pin "2") (pinfunction "B_2") (pintype "input"))
    )
    (net (code "151") (name "U_DMA_0") (class "Default")
      (node (ref "RN5") (pin "1") (pinfunction "1_1") (pintype "passive"))
      (node (ref "U_ADDR_MUX_0") (pin "15") (pinfunction "D4_15") (pintype "input"))
      (node (ref "U_DMA_SW") (pin "8") (pinfunction "8_8") (pintype "passive"))
    )
    (net (code "152") (name "U_DMA_1") (class "Default")
      (node (ref "RN5") (pin "2") (pinfunction "1_2") (pintype "passive"))
      (node (ref "U_ADDR_MUX_1") (pin "15") (pinfunction "D4_15") (pintype "input"))
      (node (ref "U_DMA_SW") (pin "7") (pinfunction "7_7") (pintype "passive"))
    )
    (net (code "153") (name "U_DMA_2") (class "Default")
      (node (ref "RN5") (pin "3") (pinfunction "1_3") (pintype "passive"))
      (node (ref "U_ADDR_MUX_2") (pin "15") (pinfunction "D4_15") (pintype "input"))
      (node (ref "U_DMA_SW") (pin "6") (pinfunction "6_6") (pintype "passive"))
    )
    (net (code "154") (name "U_DMA_3") (class "Default")
      (node (ref "RN5") (pin "4") (pinfunction "1_4") (pintype "passive"))
      (node (ref "U_ADDR_MUX_3") (pin "15") (pinfunction "D4_15") (pintype "input"))
      (node (ref "U_DMA_SW") (pin "5") (pinfunction "5_5") (pintype "passive"))
    )
    (net (code "155") (name "U_DMA_4") (class "Default")
      (node (ref "RN5") (pin "5") (pinfunction "1_5") (pintype "passive"))
      (node (ref "U_ADDR_MUX_4") (pin "15") (pinfunction "D4_15") (pintype "input"))
      (node (ref "U_DMA_SW") (pin "4") (pinfunction "4_4") (pintype "passive"))
    )
    (net (code "156") (name "U_DMA_5") (class "Default")
      (node (ref "RN5") (pin "6") (pinfunction "1_6") (pintype "passive"))
      (node (ref "U_ADDR_MUX_5") (pin "15") (pinfunction "D4_15") (pintype "input"))
      (node (ref "U_DMA_SW") (pin "3") (pinfunction "3_3") (pintype "passive"))
    )
    (net (code "157") (name "U_DMA_6") (class "Default")
      (node (ref "RN5") (pin "7") (pinfunction "1_7") (pintype "passive"))
      (node (ref "U_ADDR_MUX_6") (pin "15") (pinfunction "D4_15") (pintype "input"))
      (node (ref "U_DMA_SW") (pin "2") (pinfunction "2_2") (pintype "passive"))
    )
    (net (code "158") (name "U_DMA_7") (class "Default")
      (node (ref "RN5") (pin "8") (pinfunction "1_8") (pintype "passive"))
      (node (ref "U_ADDR_MUX_7") (pin "15") (pinfunction "D4_15") (pintype "input"))
      (node (ref "U_DMA_SW") (pin "1") (pinfunction "1_1") (pintype "passive"))
    )
    (net (code "159") (name "U_FETCH_0") (class "Default")
      (node (ref "RN3") (pin "1") (pinfunction "1_1") (pintype "passive"))
      (node (ref "U_ADDR_MUX_0") (pin "2") (pinfunction "D2_2") (pintype "input"))
      (node (ref "U_FETCH_SW") (pin "8") (pinfunction "8_8") (pintype "passive"))
    )
    (net (code "160") (name "U_FETCH_1") (class "Default")
      (node (ref "RN3") (pin "2") (pinfunction "1_2") (pintype "passive"))
      (node (ref "U_ADDR_MUX_1") (pin "2") (pinfunction "D2_2") (pintype "input"))
      (node (ref "U_FETCH_SW") (pin "7") (pinfunction "7_7") (pintype "passive"))
    )
    (net (code "161") (name "U_FETCH_2") (class "Default")
      (node (ref "RN3") (pin "3") (pinfunction "1_3") (pintype "passive"))
      (node (ref "U_ADDR_MUX_2") (pin "2") (pinfunction "D2_2") (pintype "input"))
      (node (ref "U_FETCH_SW") (pin "6") (pinfunction "6_6") (pintype "passive"))
    )
    (net (code "162") (name "U_FETCH_3") (class "Default")
      (node (ref "RN3") (pin "4") (pinfunction "1_4") (pintype "passive"))
      (node (ref "U_ADDR_MUX_3") (pin "2") (pinfunction "D2_2") (pintype "input"))
      (node (ref "U_FETCH_SW") (pin "5") (pinfunction "5_5") (pintype "passive"))
    )
    (net (code "163") (name "U_FETCH_4") (class "Default")
      (node (ref "RN3") (pin "5") (pinfunction "1_5") (pintype "passive"))
      (node (ref "U_ADDR_MUX_4") (pin "2") (pinfunction "D2_2") (pintype "input"))
      (node (ref "U_FETCH_SW") (pin "4") (pinfunction "4_4") (pintype "passive"))
    )
    (net (code "164") (name "U_FETCH_5") (class "Default")
      (node (ref "RN3") (pin "6") (pinfunction "1_6") (pintype "passive"))
      (node (ref "U_ADDR_MUX_5") (pin "2") (pinfunction "D2_2") (pintype "input"))
      (node (ref "U_FETCH_SW") (pin "3") (pinfunction "3_3") (pintype "passive"))
    )
    (net (code "165") (name "U_FETCH_6") (class "Default")
      (node (ref "RN3") (pin "7") (pinfunction "1_7") (pintype "passive"))
      (node (ref "U_ADDR_MUX_6") (pin "2") (pinfunction "D2_2") (pintype "input"))
      (node (ref "U_FETCH_SW") (pin "2") (pinfunction "2_2") (pintype "passive"))
    )
    (net (code "166") (name "U_FETCH_7") (class "Default")
      (node (ref "RN3") (pin "8") (pinfunction "1_8") (pintype "passive"))
      (node (ref "U_ADDR_MUX_7") (pin "2") (pinfunction "D2_2") (pintype "input"))
      (node (ref "U_FETCH_SW") (pin "1") (pinfunction "1_1") (pintype "passive"))
    )
    (net (code "167") (name "U_INT_0") (class "Default")
      (node (ref "RN4") (pin "1") (pinfunction "1_1") (pintype "passive"))
      (node (ref "U_ADDR_MUX_0") (pin "14") (pinfunction "D5_14") (pintype "input"))
      (node (ref "U_INT_SW") (pin "8") (pinfunction "8_8") (pintype "passive"))
    )
    (net (code "168") (name "U_INT_1") (class "Default")
      (node (ref "RN4") (pin "2") (pinfunction "1_2") (pintype "passive"))
      (node (ref "U_ADDR_MUX_1") (pin "14") (pinfunction "D5_14") (pintype "input"))
      (node (ref "U_INT_SW") (pin "7") (pinfunction "7_7") (pintype "passive"))
    )
    (net (code "169") (name "U_INT_2") (class "Default")
      (node (ref "RN4") (pin "3") (pinfunction "1_3") (pintype "passive"))
      (node (ref "U_ADDR_MUX_2") (pin "14") (pinfunction "D5_14") (pintype "input"))
      (node (ref "U_INT_SW") (pin "6") (pinfunction "6_6") (pintype "passive"))
    )
    (net (code "170") (name "U_INT_3") (class "Default")
      (node (ref "RN4") (pin "4") (pinfunction "1_4") (pintype "passive"))
      (node (ref "U_ADDR_MUX_3") (pin "14") (pinfunction "D5_14") (pintype "input"))
      (node (ref "U_INT_SW") (pin "5") (pinfunction "5_5") (pintype "passive"))
    )
    (net (code "171") (name "U_INT_4") (class "Default")
      (node (ref "RN4") (pin "5") (pinfunction "1_5") (pintype "passive"))
      (node (ref "U_ADDR_MUX_4") (pin "14") (pinfunction "D5_14") (pintype "input"))
      (node (ref "U_INT_SW") (pin "4") (pinfunction "4_4") (pintype "passive"))
    )
    (net (code "172") (name "U_INT_5") (class "Default")
      (node (ref "RN4") (pin "6") (pinfunction "1_6") (pintype "passive"))
      (node (ref "U_ADDR_MUX_5") (pin "14") (pinfunction "D5_14") (pintype "input"))
      (node (ref "U_INT_SW") (pin "3") (pinfunction "3_3") (pintype "passive"))
    )
    (net (code "173") (name "U_INT_6") (class "Default")
      (node (ref "RN4") (pin "7") (pinfunction "1_7") (pintype "passive"))
      (node (ref "U_ADDR_MUX_6") (pin "14") (pinfunction "D5_14") (pintype "input"))
      (node (ref "U_INT_SW") (pin "2") (pinfunction "2_2") (pintype "passive"))
    )
    (net (code "174") (name "U_INT_7") (class "Default")
      (node (ref "RN4") (pin "8") (pinfunction "1_8") (pintype "passive"))
      (node (ref "U_ADDR_MUX_7") (pin "14") (pinfunction "D5_14") (pintype "input"))
      (node (ref "U_INT_SW") (pin "1") (pinfunction "1_1") (pintype "passive"))
    )
    (net (code "175") (name "U_OF") (class "Default")
      (node (ref "COND_MUX_1") (pin "11") (pinfunction "2C1_11") (pintype "input"))
      (node (ref "U_FLAGS") (pin "9") (pinfunction "Q4_9") (pintype "output"))
      (node (ref "U_FLAGS_MUX_3") (pin "2") (pinfunction "1A_2") (pintype "input"))
    )
    (net (code "176") (name "U_OFFSET0") (class "Default")
      (node (ref "U_ADDER_MUX_0") (pin "3") (pinfunction "1B_3") (pintype "input"))
    )
    (net (code "177") (name "U_OFFSET1") (class "Default")
      (node (ref "U_ADDER_MUX_0") (pin "6") (pinfunction "2B_6") (pintype "input"))
    )
    (net (code "178") (name "U_OFFSET2") (class "Default")
      (node (ref "U_ADDER_MUX_0") (pin "10") (pinfunction "3B_10") (pintype "input"))
    )
    (net (code "179") (name "U_OFFSET3") (class "Default")
      (node (ref "U_ADDER_MUX_0") (pin "13") (pinfunction "4B_13") (pintype "input"))
    )
    (net (code "180") (name "U_OFFSET4") (class "Default")
      (node (ref "U_ADDER_MUX_1") (pin "3") (pinfunction "1B_3") (pintype "input"))
    )
    (net (code "181") (name "U_OFFSET5") (class "Default")
      (node (ref "U_ADDER_MUX_1") (pin "6") (pinfunction "2B_6") (pintype "input"))
    )
    (net (code "182") (name "U_OFFSET6") (class "Default")
      (node (ref "U_ADDER_MUX_1") (pin "10") (pinfunction "3B_10") (pintype "input"))
      (node (ref "U_ADDER_MUX_1") (pin "13") (pinfunction "4B_13") (pintype "input"))
      (node (ref "U_ADDER_MUX_2") (pin "10") (pinfunction "3B_10") (pintype "input"))
      (node (ref "U_ADDER_MUX_2") (pin "13") (pinfunction "4B_13") (pintype "input"))
      (node (ref "U_ADDER_MUX_2") (pin "3") (pinfunction "1B_3") (pintype "input"))
      (node (ref "U_ADDER_MUX_2") (pin "6") (pinfunction "2B_6") (pintype "input"))
      (node (ref "U_ADDER_MUX_3") (pin "10") (pinfunction "3B_10") (pintype "input"))
      (node (ref "U_ADDER_MUX_3") (pin "13") (pinfunction "4B_13") (pintype "input"))
      (node (ref "U_ADDER_MUX_3") (pin "3") (pinfunction "1B_3") (pintype "input"))
      (node (ref "U_ADDER_MUX_3") (pin "6") (pinfunction "2B_6") (pintype "input"))
    )
    (net (code "183") (name "U_OF_IN_SRC") (class "Default")
      (node (ref "U_FLAGS_MUX_3") (pin "1") (pinfunction "~{A}/B_1") (pintype "input"))
    )
    (net (code "184") (name "U_SF") (class "Default")
      (node (ref "COND_MUX_1") (pin "5") (pinfunction "1C1_5") (pintype "input"))
      (node (ref "U_FLAGS") (pin "6") (pinfunction "Q3_6") (pintype "output"))
      (node (ref "U_FLAGS_MUX_2") (pin "2") (pinfunction "1A_2") (pintype "input"))
    )
    (net (code "185") (name "U_SF_IN_SRC") (class "Default")
      (node (ref "U_FLAGS_MUX_2") (pin "1") (pinfunction "~{A}/B_1") (pintype "input"))
    )
    (net (code "186") (name "U_TRAP_0") (class "Default")
      (node (ref "RN2") (pin "1") (pinfunction "1_1") (pintype "passive"))
      (node (ref "U_ADDR_MUX_0") (pin "1") (pinfunction "D3_1") (pintype "input"))
      (node (ref "U_TRAP_SW") (pin "8") (pinfunction "8_8") (pintype "passive"))
    )
    (net (code "187") (name "U_TRAP_1") (class "Default")
      (node (ref "RN2") (pin "2") (pinfunction "1_2") (pintype "passive"))
      (node (ref "U_ADDR_MUX_1") (pin "1") (pinfunction "D3_1") (pintype "input"))
      (node (ref "U_TRAP_SW") (pin "7") (pinfunction "7_7") (pintype "passive"))
    )
    (net (code "188") (name "U_TRAP_2") (class "Default")
      (node (ref "RN2") (pin "3") (pinfunction "1_3") (pintype "passive"))
      (node (ref "U_ADDR_MUX_2") (pin "1") (pinfunction "D3_1") (pintype "input"))
      (node (ref "U_TRAP_SW") (pin "6") (pinfunction "6_6") (pintype "passive"))
    )
    (net (code "189") (name "U_TRAP_3") (class "Default")
      (node (ref "RN2") (pin "4") (pinfunction "1_4") (pintype "passive"))
      (node (ref "U_ADDR_MUX_3") (pin "1") (pinfunction "D3_1") (pintype "input"))
      (node (ref "U_TRAP_SW") (pin "5") (pinfunction "5_5") (pintype "passive"))
    )
    (net (code "190") (name "U_TRAP_4") (class "Default")
      (node (ref "RN2") (pin "5") (pinfunction "1_5") (pintype "passive"))
      (node (ref "U_ADDR_MUX_4") (pin "1") (pinfunction "D3_1") (pintype "input"))
      (node (ref "U_TRAP_SW") (pin "4") (pinfunction "4_4") (pintype "passive"))
    )
    (net (code "191") (name "U_TRAP_5") (class "Default")
      (node (ref "RN2") (pin "6") (pinfunction "1_6") (pintype "passive"))
      (node (ref "U_ADDR_MUX_5") (pin "1") (pinfunction "D3_1") (pintype "input"))
      (node (ref "U_TRAP_SW") (pin "3") (pinfunction "3_3") (pintype "passive"))
    )
    (net (code "192") (name "U_TRAP_6") (class "Default")
      (node (ref "RN2") (pin "7") (pinfunction "1_7") (pintype "passive"))
      (node (ref "U_ADDR_MUX_6") (pin "1") (pinfunction "D3_1") (pintype "input"))
      (node (ref "U_TRAP_SW") (pin "2") (pinfunction "2_2") (pintype "passive"))
    )
    (net (code "193") (name "U_TRAP_7") (class "Default")
      (node (ref "RN2") (pin "8") (pinfunction "1_8") (pintype "passive"))
      (node (ref "U_ADDR_MUX_7") (pin "1") (pinfunction "D3_1") (pintype "input"))
      (node (ref "U_TRAP_SW") (pin "1") (pinfunction "1_1") (pintype "passive"))
    )
    (net (code "194") (name "U_ZF") (class "Default")
      (node (ref "2AND_0") (pin "2") (pinfunction "I1_2") (pintype "input"))
      (node (ref "2AND_1") (pin "1") (pinfunction "I0_1") (pintype "input"))
      (node (ref "COND_MUX_0") (pin "5") (pinfunction "1C1_5") (pintype "input"))
      (node (ref "U_FLAGS") (pin "2") (pinfunction "Q1_2") (pintype "output"))
      (node (ref "U_FLAGS_MUX_0") (pin "6") (pinfunction "1C0_6") (pintype "input"))
    )
    (net (code "195") (name "U_ZF_IN_SRC_0") (class "Default")
      (node (ref "U_FLAGS_MUX_0") (pin "14") (pinfunction "A_14") (pintype "input"))
    )
    (net (code "196") (name "U_ZF_IN_SRC_1") (class "Default")
      (node (ref "U_FLAGS_MUX_0") (pin "2") (pinfunction "B_2") (pintype "input"))
    )
    (net (code "197") (name "VCC") (class "Default")
      (node (ref "U_ADDER_MUX_0") (pin "2") (pinfunction "1A_2") (pintype "input"))
      (node (ref "U_DMA_SW") (pin "10") (pinfunction "10_10") (pintype "passive"))
      (node (ref "U_DMA_SW") (pin "11") (pinfunction "11_11") (pintype "passive"))
      (node (ref "U_DMA_SW") (pin "12") (pinfunction "12_12") (pintype "passive"))
      (node (ref "U_DMA_SW") (pin "13") (pinfunction "13_13") (pintype "passive"))
      (node (ref "U_DMA_SW") (pin "14") (pinfunction "14_14") (pintype "passive"))
      (node (ref "U_DMA_SW") (pin "15") (pinfunction "15_15") (pintype "passive"))
      (node (ref "U_DMA_SW") (pin "16") (pinfunction "16_16") (pintype "passive"))
      (node (ref "U_DMA_SW") (pin "9") (pinfunction "9_9") (pintype "passive"))
      (node (ref "U_FETCH_SW") (pin "10") (pinfunction "10_10") (pintype "passive"))
      (node (ref "U_FETCH_SW") (pin "11") (pinfunction "11_11") (pintype "passive"))
      (node (ref "U_FETCH_SW") (pin "12") (pinfunction "12_12") (pintype "passive"))
      (node (ref "U_FETCH_SW") (pin "13") (pinfunction "13_13") (pintype "passive"))
      (node (ref "U_FETCH_SW") (pin "14") (pinfunction "14_14") (pintype "passive"))
      (node (ref "U_FETCH_SW") (pin "15") (pinfunction "15_15") (pintype "passive"))
      (node (ref "U_FETCH_SW") (pin "16") (pinfunction "16_16") (pintype "passive"))
      (node (ref "U_FETCH_SW") (pin "9") (pinfunction "9_9") (pintype "passive"))
      (node (ref "U_FLAGS") (pin "1") (pinfunction "CLR_1") (pintype "input"))
      (node (ref "U_INT_SW") (pin "10") (pinfunction "10_10") (pintype "passive"))
      (node (ref "U_INT_SW") (pin "11") (pinfunction "11_11") (pintype "passive"))
      (node (ref "U_INT_SW") (pin "12") (pinfunction "12_12") (pintype "passive"))
      (node (ref "U_INT_SW") (pin "13") (pinfunction "13_13") (pintype "passive"))
      (node (ref "U_INT_SW") (pin "14") (pinfunction "14_14") (pintype "passive"))
      (node (ref "U_INT_SW") (pin "15") (pinfunction "15_15") (pintype "passive"))
      (node (ref "U_INT_SW") (pin "16") (pinfunction "16_16") (pintype "passive"))
      (node (ref "U_INT_SW") (pin "9") (pinfunction "9_9") (pintype "passive"))
      (node (ref "U_TRAP_SW") (pin "10") (pinfunction "10_10") (pintype "passive"))
      (node (ref "U_TRAP_SW") (pin "11") (pinfunction "11_11") (pintype "passive"))
      (node (ref "U_TRAP_SW") (pin "12") (pinfunction "12_12") (pintype "passive"))
      (node (ref "U_TRAP_SW") (pin "13") (pinfunction "13_13") (pintype "passive"))
      (node (ref "U_TRAP_SW") (pin "14") (pinfunction "14_14") (pintype "passive"))
      (node (ref "U_TRAP_SW") (pin "15") (pinfunction "15_15") (pintype "passive"))
      (node (ref "U_TRAP_SW") (pin "16") (pinfunction "16_16") (pintype "passive"))
      (node (ref "U_TRAP_SW") (pin "9") (pinfunction "9_9") (pintype "passive"))
    )
    (net (code "198") (name "ZF") (class "Default")
      (node (ref "COND_MUX_0") (pin "6") (pinfunction "1C0_6") (pintype "input"))
    )
    (net (code "199") (name "ZF_FROM_ALU") (class "Default")
      (node (ref "2AND_0") (pin "1") (pinfunction "I0_1") (pintype "input"))
      (node (ref "2AND_1") (pin "2") (pinfunction "I1_2") (pintype "input"))
      (node (ref "COND_MUX_0") (pin "4") (pinfunction "1C2_4") (pintype "input"))
      (node (ref "U_FLAGS_MUX_0") (pin "5") (pinfunction "1C1_5") (pintype "input"))
    )
    (net (code "200") (name "unconnected-(COND_MUX_2A-W-Pad6)") (class "Default")
      (node (ref "COND_MUX_2") (pin "6") (pinfunction "W_6") (pintype "output"))
    )
    (net (code "201") (name "unconnected-(IR_HA-5Q-Pad12)") (class "Default")
      (node (ref "IR_H") (pin "12") (pinfunction "5Q_12") (pintype "output"))
    )
    (net (code "202") (name "unconnected-(IR_HA-6Q-Pad15)") (class "Default")
      (node (ref "IR_H") (pin "15") (pinfunction "6Q_15") (pintype "output"))
    )
    (net (code "203") (name "unconnected-(IR_HA-7Q-Pad16)") (class "Default")
      (node (ref "IR_H") (pin "16") (pinfunction "7Q_16") (pintype "output"))
    )
    (net (code "204") (name "unconnected-(IR_HA-8Q-Pad19)") (class "Default")
      (node (ref "IR_H") (pin "19") (pinfunction "8Q_19") (pintype "output"))
    )
    (net (code "205") (name "unconnected-(U_ADDER_3A-C4-Pad9)") (class "Default")
      (node (ref "U_ADDER_3") (pin "9") (pinfunction "C4_9") (pintype "output"))
    )
    (net (code "206") (name "unconnected-(U_ADDR_HA-CLR-Pad1)") (class "Default")
      (node (ref "U_ADDR_H") (pin "1") (pinfunction "CLR_1") (pintype "input"))
    )
    (net (code "207") (name "unconnected-(U_ADDR_LA-CLR-Pad1)") (class "Default")
      (node (ref "U_ADDR_L") (pin "1") (pinfunction "CLR_1") (pintype "input"))
    )
    (net (code "208") (name "unconnected-(U_ADDR_MUX_0A-W-Pad6)") (class "Default")
      (node (ref "U_ADDR_MUX_0") (pin "6") (pinfunction "W_6") (pintype "output"))
    )
    (net (code "209") (name "unconnected-(U_ADDR_MUX_1A-W-Pad6)") (class "Default")
      (node (ref "U_ADDR_MUX_1") (pin "6") (pinfunction "W_6") (pintype "output"))
    )
    (net (code "210") (name "unconnected-(U_ADDR_MUX_2A-W-Pad6)") (class "Default")
      (node (ref "U_ADDR_MUX_2") (pin "6") (pinfunction "W_6") (pintype "output"))
    )
    (net (code "211") (name "unconnected-(U_ADDR_MUX_3A-W-Pad6)") (class "Default")
      (node (ref "U_ADDR_MUX_3") (pin "6") (pinfunction "W_6") (pintype "output"))
    )
    (net (code "212") (name "unconnected-(U_ADDR_MUX_4A-W-Pad6)") (class "Default")
      (node (ref "U_ADDR_MUX_4") (pin "6") (pinfunction "W_6") (pintype "output"))
    )
    (net (code "213") (name "unconnected-(U_ADDR_MUX_5A-W-Pad6)") (class "Default")
      (node (ref "U_ADDR_MUX_5") (pin "6") (pinfunction "W_6") (pintype "output"))
    )
    (net (code "214") (name "unconnected-(U_ADDR_MUX_6A-W-Pad6)") (class "Default")
      (node (ref "U_ADDR_MUX_6") (pin "6") (pinfunction "W_6") (pintype "output"))
    )
    (net (code "215") (name "unconnected-(U_ADDR_MUX_7A-W-Pad6)") (class "Default")
      (node (ref "U_ADDR_MUX_7") (pin "6") (pinfunction "W_6") (pintype "output"))
    )
    (net (code "216") (name "unconnected-(U_ADDR_MUX_8A-W-Pad6)") (class "Default")
      (node (ref "U_ADDR_MUX_8") (pin "6") (pinfunction "W_6") (pintype "output"))
    )
    (net (code "217") (name "unconnected-(U_ADDR_MUX_9A-W-Pad6)") (class "Default")
      (node (ref "U_ADDR_MUX_9") (pin "6") (pinfunction "W_6") (pintype "output"))
    )
    (net (code "218") (name "unconnected-(U_ADDR_MUX_10A-W-Pad6)") (class "Default")
      (node (ref "U_ADDR_MUX_10") (pin "6") (pinfunction "W_6") (pintype "output"))
    )
    (net (code "219") (name "unconnected-(U_ADDR_MUX_11A-W-Pad6)") (class "Default")
      (node (ref "U_ADDR_MUX_11") (pin "6") (pinfunction "W_6") (pintype "output"))
    )
    (net (code "220") (name "unconnected-(U_ADDR_MUX_12A-W-Pad6)") (class "Default")
      (node (ref "U_ADDR_MUX_12") (pin "6") (pinfunction "W_6") (pintype "output"))
    )
    (net (code "221") (name "unconnected-(U_ADDR_MUX_13A-W-Pad6)") (class "Default")
      (node (ref "U_ADDR_MUX_13") (pin "6") (pinfunction "W_6") (pintype "output"))
    )
    (net (code "222") (name "unconnected-(U_ADDR_MUX_14A-W-Pad6)") (class "Default")
      (node (ref "U_ADDR_MUX_14") (pin "6") (pinfunction "W_6") (pintype "output"))
    )
    (net (code "223") (name "unconnected-(U_ADDR_MUX_15A-W-Pad6)") (class "Default")
      (node (ref "U_ADDR_MUX_15") (pin "6") (pinfunction "W_6") (pintype "output"))
    )
    (net (code "224") (name "unconnected-(U_FLAGSA-CLK-Pad11)") (class "Default")
      (node (ref "U_FLAGS") (pin "11") (pinfunction "CLK_11") (pintype "input"))
    )
    (net (code "225") (name "unconnected-(U_FLAGSA-Q5-Pad12)") (class "Default")
      (node (ref "U_FLAGS") (pin "12") (pinfunction "Q5_12") (pintype "output"))
    )
    (net (code "226") (name "unconnected-(U_FLAGSA-Q6-Pad15)") (class "Default")
      (node (ref "U_FLAGS") (pin "15") (pinfunction "Q6_15") (pintype "output"))
    )
    (net (code "227") (name "unconnected-(U_FLAGSA-Q7-Pad16)") (class "Default")
      (node (ref "U_FLAGS") (pin "16") (pinfunction "Q7_16") (pintype "output"))
    )
    (net (code "228") (name "unconnected-(U_FLAGSA-Q8-Pad19)") (class "Default")
      (node (ref "U_FLAGS") (pin "19") (pinfunction "Q8_19") (pintype "output"))
    )
    (net (code "229") (name "unconnected-(U_FLAGS_MUX_0A-2Y-Pad9)") (class "Default")
      (node (ref "U_FLAGS_MUX_0") (pin "9") (pinfunction "2Y_9") (pintype "output"))
    )
    (net (code "230") (name "unconnected-(U_FLAGS_MUX_1A-2Y-Pad9)") (class "Default")
      (node (ref "U_FLAGS_MUX_1") (pin "9") (pinfunction "2Y_9") (pintype "output"))
    )
    (net (code "231") (name "unconnected-(U_FLAGS_MUX_2A-2Y-Pad7)") (class "Default")
      (node (ref "U_FLAGS_MUX_2") (pin "7") (pinfunction "2Y_7") (pintype "tri_state"))
    )
    (net (code "232") (name "unconnected-(U_FLAGS_MUX_2A-3Y-Pad9)") (class "Default")
      (node (ref "U_FLAGS_MUX_2") (pin "9") (pinfunction "3Y_9") (pintype "tri_state"))
    )
    (net (code "233") (name "unconnected-(U_FLAGS_MUX_2A-4Y-Pad12)") (class "Default")
      (node (ref "U_FLAGS_MUX_2") (pin "12") (pinfunction "4Y_12") (pintype "tri_state"))
    )
    (net (code "234") (name "unconnected-(U_FLAGS_MUX_3A-2Y-Pad7)") (class "Default")
      (node (ref "U_FLAGS_MUX_3") (pin "7") (pinfunction "2Y_7") (pintype "tri_state"))
    )
    (net (code "235") (name "unconnected-(U_FLAGS_MUX_3A-3Y-Pad9)") (class "Default")
      (node (ref "U_FLAGS_MUX_3") (pin "9") (pinfunction "3Y_9") (pintype "tri_state"))
    )
    (net (code "236") (name "unconnected-(U_FLAGS_MUX_3A-4Y-Pad12)") (class "Default")
      (node (ref "U_FLAGS_MUX_3") (pin "12") (pinfunction "4Y_12") (pintype "tri_state"))
    )
  )
)
